# UMDK.net
KiCad netlist of a schematic drawn in Altium Designer
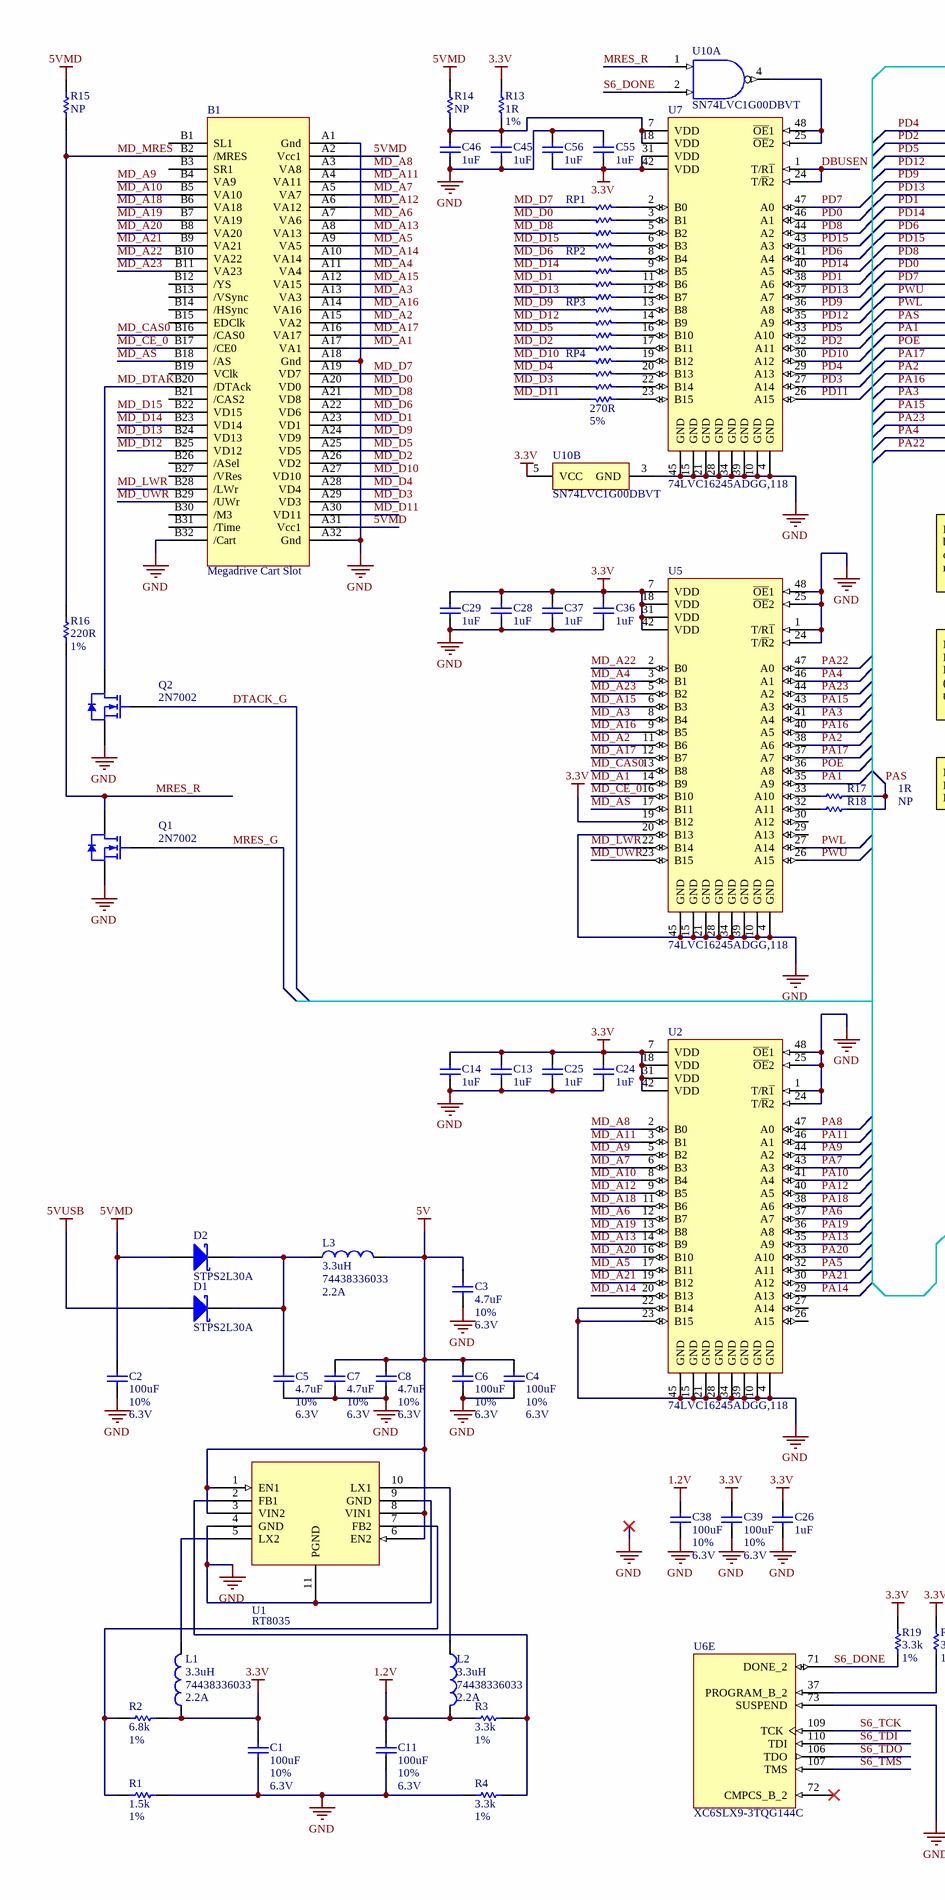
[diagram p0: UMDK.SchDoc, left]
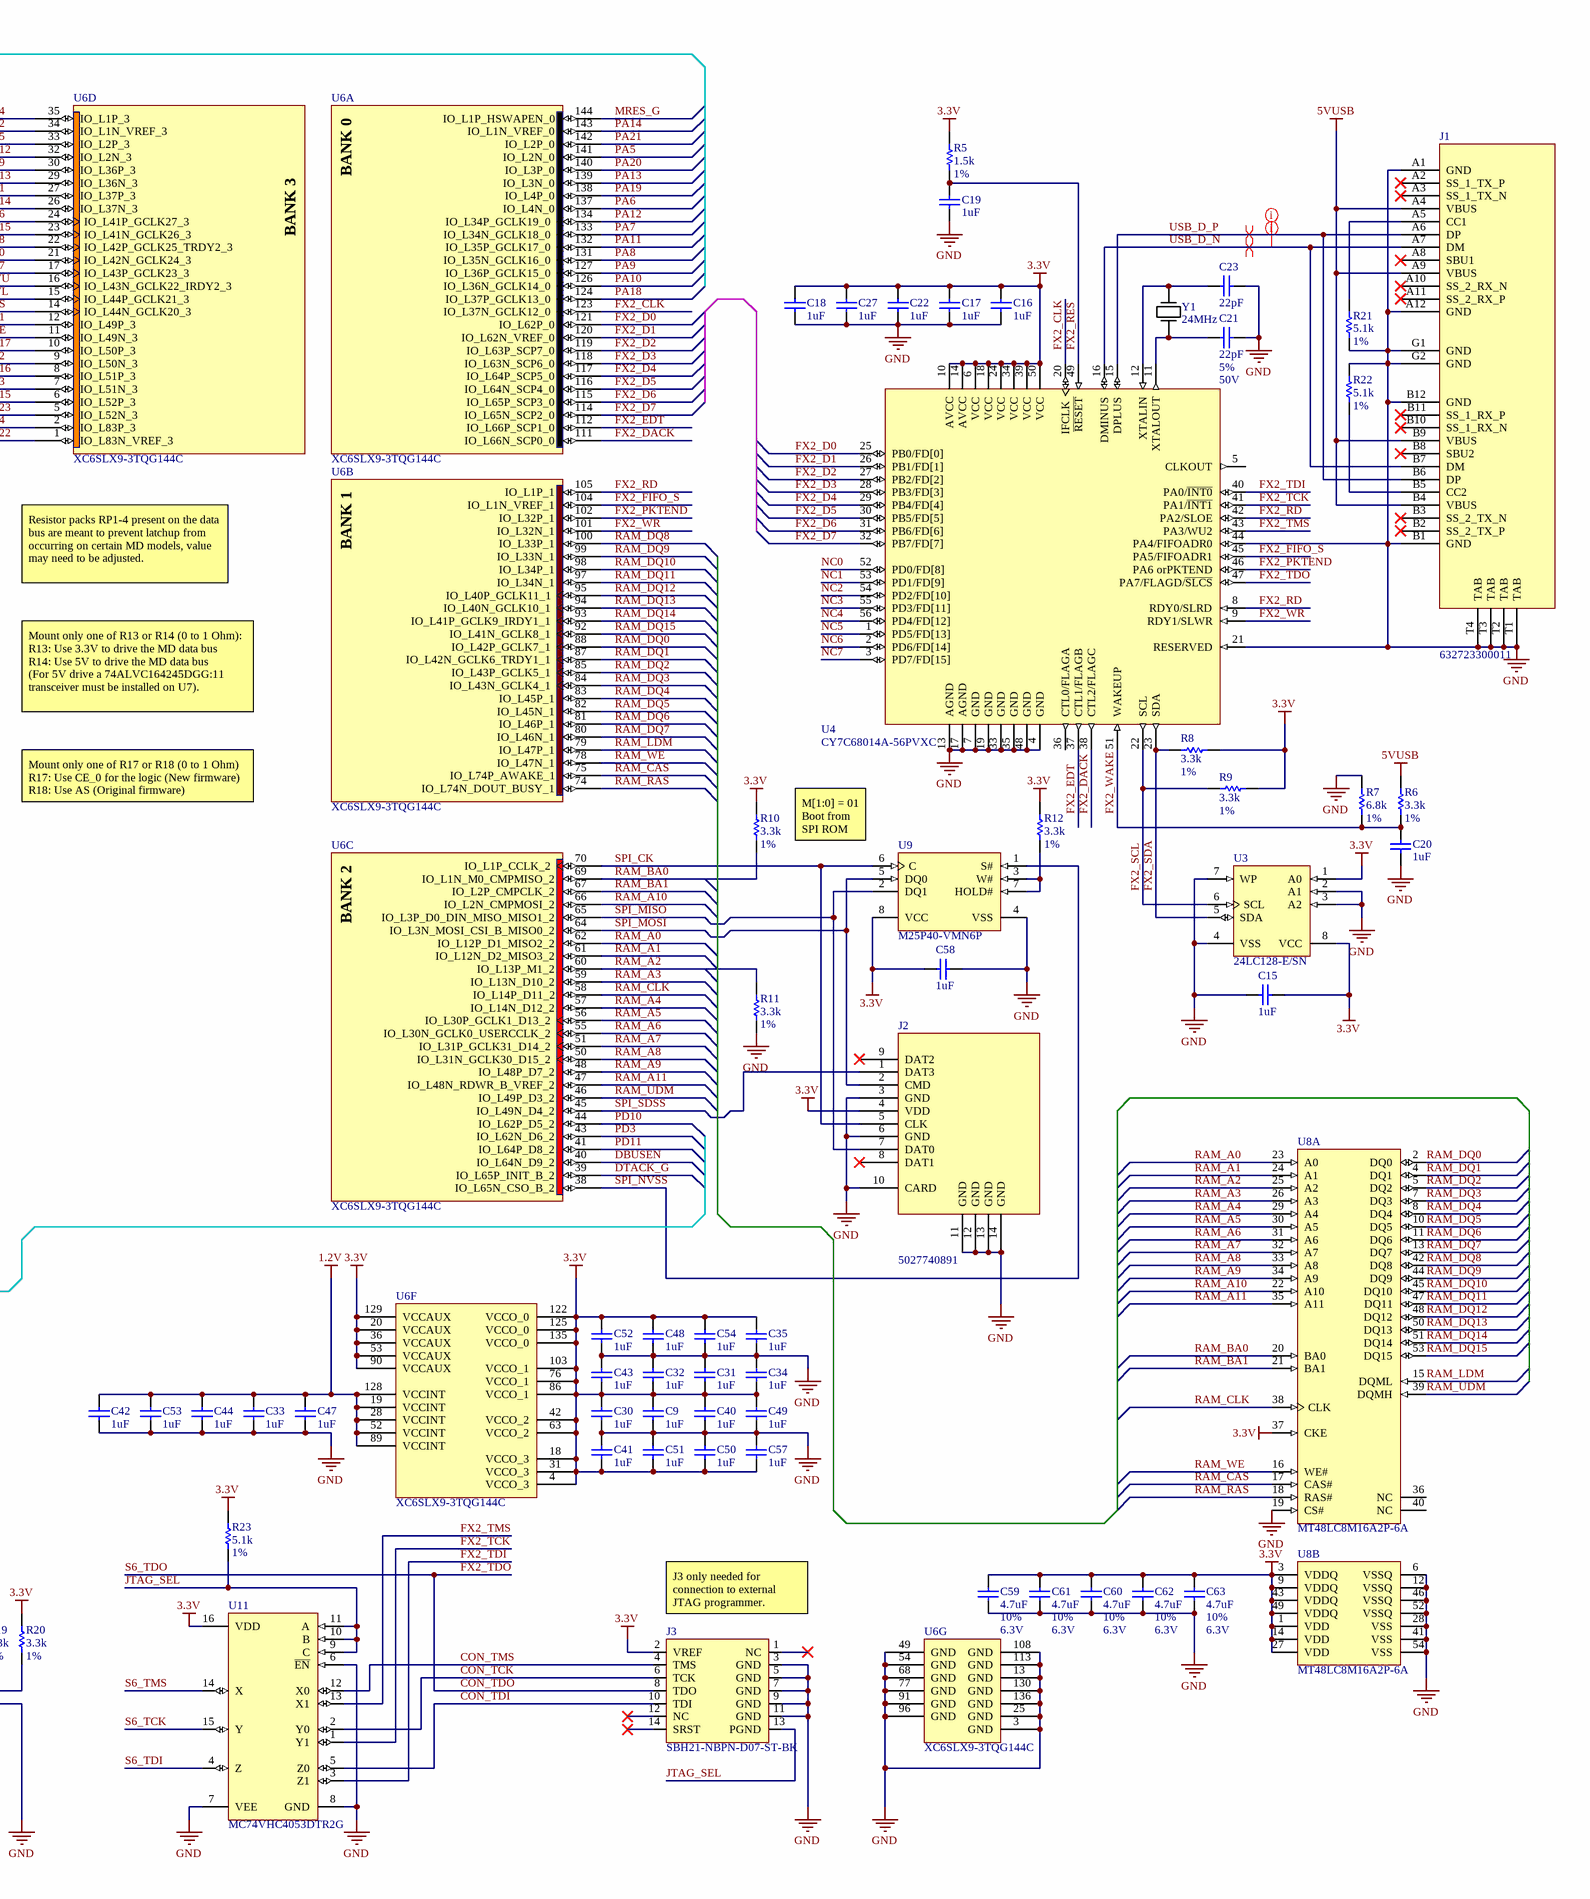
[diagram p1: UMDK.SchDoc, right]

(export (version "E")
  (design (tool "Eeschema 10.0.6"))
  (components
    (comp (ref "B1")
      (value "Megadrive Cart Slot")
      (footprint "MD CART EDGE")
      (description "Megadrive Cart Edge Connector")
      (libsource (lib "UMDK") (part "Megadrive Cart Slot"))
    )
    (comp (ref "C1")
      (value "100uF")
      (footprint "C-1210")
      (description "SMD Capacitor")
      (fields
        (field (name "MANUFACTURER PART NUMBER") "C1210C107M9PAC7800")
        (field (name "MANUFACTURER") "Kemet")
        (field (name "TOLERANCE") "10%")
        (field (name "VOLTAGE") "6.3V")
      )
      (libsource (lib "UMDK") (part "CAP_SMD"))
    )
    (comp (ref "C2")
      (value "100uF")
      (footprint "C-1210")
      (description "SMD Capacitor")
      (fields
        (field (name "MANUFACTURER PART NUMBER") "C1210C107M9PAC7800")
        (field (name "MANUFACTURER") "Kemet")
        (field (name "TOLERANCE") "10%")
        (field (name "VOLTAGE") "6.3V")
      )
      (libsource (lib "UMDK") (part "CAP_SMD"))
    )
    (comp (ref "C3")
      (value "4.7uF")
      (footprint "C-0603")
      (description "SMD Capacitor")
      (fields
        (field (name "MANUFACTURER PART NUMBER") "C0603C475K9PAC7867")
        (field (name "MANUFACTURER") "Kemet")
        (field (name "TOLERANCE") "10%")
        (field (name "VOLTAGE") "6.3V")
      )
      (libsource (lib "UMDK") (part "CAP_SMD"))
    )
    (comp (ref "C4")
      (value "100uF")
      (footprint "C-1210")
      (description "SMD Capacitor")
      (fields
        (field (name "MANUFACTURER PART NUMBER") "C1210C107M9PAC7800")
        (field (name "MANUFACTURER") "Kemet")
        (field (name "TOLERANCE") "10%")
        (field (name "VOLTAGE") "6.3V")
      )
      (libsource (lib "UMDK") (part "CAP_SMD"))
    )
    (comp (ref "C5")
      (value "4.7uF")
      (footprint "C-0603")
      (description "SMD Capacitor")
      (fields
        (field (name "MANUFACTURER PART NUMBER") "C0603C475K9PAC7867")
        (field (name "MANUFACTURER") "Kemet")
        (field (name "TOLERANCE") "10%")
        (field (name "VOLTAGE") "6.3V")
      )
      (libsource (lib "UMDK") (part "CAP_SMD"))
    )
    (comp (ref "C6")
      (value "100uF")
      (footprint "C-1210")
      (description "SMD Capacitor")
      (fields
        (field (name "MANUFACTURER PART NUMBER") "C1210C107M9PAC7800")
        (field (name "MANUFACTURER") "Kemet")
        (field (name "TOLERANCE") "10%")
        (field (name "VOLTAGE") "6.3V")
      )
      (libsource (lib "UMDK") (part "CAP_SMD"))
    )
    (comp (ref "C7")
      (value "4.7uF")
      (footprint "C-0603")
      (description "SMD Capacitor")
      (fields
        (field (name "MANUFACTURER PART NUMBER") "C0603C475K9PAC7867")
        (field (name "MANUFACTURER") "Kemet")
        (field (name "TOLERANCE") "10%")
        (field (name "VOLTAGE") "6.3V")
      )
      (libsource (lib "UMDK") (part "CAP_SMD"))
    )
    (comp (ref "C8")
      (value "4.7uF")
      (footprint "C-0603")
      (description "SMD Capacitor")
      (fields
        (field (name "MANUFACTURER PART NUMBER") "C0603C475K9PAC7867")
        (field (name "MANUFACTURER") "Kemet")
        (field (name "TOLERANCE") "10%")
        (field (name "VOLTAGE") "6.3V")
      )
      (libsource (lib "UMDK") (part "CAP_SMD"))
    )
    (comp (ref "C9")
      (value "1uF")
      (footprint "C-0402")
      (description "SMD Capacitor")
      (fields
        (field (name "MANUFACTURER PART NUMBER") "C0402C105K9PAC7867")
        (field (name "MANUFACTURER") "Kemet")
      )
      (libsource (lib "UMDK") (part "CAP_SMD"))
    )
    (comp (ref "C11")
      (value "100uF")
      (footprint "C-1210")
      (description "SMD Capacitor")
      (fields
        (field (name "MANUFACTURER PART NUMBER") "C1210C107M9PAC7800")
        (field (name "MANUFACTURER") "Kemet")
        (field (name "TOLERANCE") "10%")
        (field (name "VOLTAGE") "6.3V")
      )
      (libsource (lib "UMDK") (part "CAP_SMD"))
    )
    (comp (ref "C13")
      (value "1uF")
      (footprint "C-0402")
      (description "SMD Capacitor")
      (fields
        (field (name "MANUFACTURER PART NUMBER") "C0402C105K9PAC7867")
        (field (name "MANUFACTURER") "Kemet")
      )
      (libsource (lib "UMDK") (part "CAP_SMD"))
    )
    (comp (ref "C14")
      (value "1uF")
      (footprint "C-0402")
      (description "SMD Capacitor")
      (fields
        (field (name "MANUFACTURER PART NUMBER") "C0402C105K9PAC7867")
        (field (name "MANUFACTURER") "Kemet")
      )
      (libsource (lib "UMDK") (part "CAP_SMD"))
    )
    (comp (ref "C15")
      (value "1uF")
      (footprint "C-0402")
      (description "SMD Capacitor")
      (fields
        (field (name "MANUFACTURER PART NUMBER") "C0402C105K9PAC7867")
        (field (name "MANUFACTURER") "Kemet")
      )
      (libsource (lib "UMDK") (part "CAP_SMD"))
    )
    (comp (ref "C16")
      (value "1uF")
      (footprint "C-0402")
      (description "SMD Capacitor")
      (fields
        (field (name "MANUFACTURER PART NUMBER") "C0402C105K9PAC7867")
        (field (name "MANUFACTURER") "Kemet")
      )
      (libsource (lib "UMDK") (part "CAP_SMD"))
    )
    (comp (ref "C17")
      (value "1uF")
      (footprint "C-0402")
      (description "SMD Capacitor")
      (fields
        (field (name "MANUFACTURER PART NUMBER") "C0402C105K9PAC7867")
        (field (name "MANUFACTURER") "Kemet")
      )
      (libsource (lib "UMDK") (part "CAP_SMD"))
    )
    (comp (ref "C18")
      (value "1uF")
      (footprint "C-0402")
      (description "SMD Capacitor")
      (fields
        (field (name "MANUFACTURER PART NUMBER") "C0402C105K9PAC7867")
        (field (name "MANUFACTURER") "Kemet")
      )
      (libsource (lib "UMDK") (part "CAP_SMD"))
    )
    (comp (ref "C19")
      (value "1uF")
      (footprint "C-0402")
      (description "SMD Capacitor")
      (fields
        (field (name "MANUFACTURER PART NUMBER") "C0402C105K9PAC7867")
        (field (name "MANUFACTURER") "Kemet")
      )
      (libsource (lib "UMDK") (part "CAP_SMD"))
    )
    (comp (ref "C20")
      (value "1uF")
      (footprint "C-0402")
      (description "SMD Capacitor")
      (fields
        (field (name "MANUFACTURER PART NUMBER") "C0402C105K9PAC7867")
        (field (name "MANUFACTURER") "Kemet")
      )
      (libsource (lib "UMDK") (part "CAP_SMD"))
    )
    (comp (ref "C21")
      (value "22pF")
      (footprint "C-0402")
      (description "SMD Capacitor")
      (fields
        (field (name "MANUFACTURER PART NUMBER") "C0402C220J5GACTU")
        (field (name "MANUFACTURER") "Kemet")
        (field (name "TOLERANCE") "5%")
        (field (name "VOLTAGE") "50V")
      )
      (libsource (lib "UMDK") (part "CAP_SMD"))
    )
    (comp (ref "C22")
      (value "1uF")
      (footprint "C-0402")
      (description "SMD Capacitor")
      (fields
        (field (name "MANUFACTURER PART NUMBER") "C0402C105K9PAC7867")
        (field (name "MANUFACTURER") "Kemet")
      )
      (libsource (lib "UMDK") (part "CAP_SMD"))
    )
    (comp (ref "C23")
      (value "22pF")
      (footprint "C-0402")
      (description "SMD Capacitor")
      (fields
        (field (name "MANUFACTURER PART NUMBER") "C0402C220J5GACTU")
        (field (name "MANUFACTURER") "Kemet")
      )
      (libsource (lib "UMDK") (part "CAP_SMD"))
    )
    (comp (ref "C24")
      (value "1uF")
      (footprint "C-0402")
      (description "SMD Capacitor")
      (fields
        (field (name "MANUFACTURER PART NUMBER") "C0402C105K9PAC7867")
        (field (name "MANUFACTURER") "Kemet")
      )
      (libsource (lib "UMDK") (part "CAP_SMD"))
    )
    (comp (ref "C25")
      (value "1uF")
      (footprint "C-0402")
      (description "SMD Capacitor")
      (fields
        (field (name "MANUFACTURER PART NUMBER") "C0402C105K9PAC7867")
        (field (name "MANUFACTURER") "Kemet")
      )
      (libsource (lib "UMDK") (part "CAP_SMD"))
    )
    (comp (ref "C26")
      (value "1uF")
      (footprint "C-0402")
      (description "SMD Capacitor")
      (fields
        (field (name "MANUFACTURER PART NUMBER") "C0402C105K9PAC7867")
        (field (name "MANUFACTURER") "Kemet")
      )
      (libsource (lib "UMDK") (part "CAP_SMD"))
    )
    (comp (ref "C27")
      (value "1uF")
      (footprint "C-0402")
      (description "SMD Capacitor")
      (fields
        (field (name "MANUFACTURER PART NUMBER") "C0402C105K9PAC7867")
        (field (name "MANUFACTURER") "Kemet")
      )
      (libsource (lib "UMDK") (part "CAP_SMD"))
    )
    (comp (ref "C28")
      (value "1uF")
      (footprint "C-0402")
      (description "SMD Capacitor")
      (fields
        (field (name "MANUFACTURER PART NUMBER") "C0402C105K9PAC7867")
        (field (name "MANUFACTURER") "Kemet")
      )
      (libsource (lib "UMDK") (part "CAP_SMD"))
    )
    (comp (ref "C29")
      (value "1uF")
      (footprint "C-0402")
      (description "SMD Capacitor")
      (fields
        (field (name "MANUFACTURER PART NUMBER") "C0402C105K9PAC7867")
        (field (name "MANUFACTURER") "Kemet")
      )
      (libsource (lib "UMDK") (part "CAP_SMD"))
    )
    (comp (ref "C30")
      (value "1uF")
      (footprint "C-0402")
      (description "SMD Capacitor")
      (fields
        (field (name "MANUFACTURER PART NUMBER") "C0402C105K9PAC7867")
        (field (name "MANUFACTURER") "Kemet")
      )
      (libsource (lib "UMDK") (part "CAP_SMD"))
    )
    (comp (ref "C31")
      (value "1uF")
      (footprint "C-0402")
      (description "SMD Capacitor")
      (fields
        (field (name "MANUFACTURER PART NUMBER") "C0402C105K9PAC7867")
        (field (name "MANUFACTURER") "Kemet")
      )
      (libsource (lib "UMDK") (part "CAP_SMD"))
    )
    (comp (ref "C32")
      (value "1uF")
      (footprint "C-0402")
      (description "SMD Capacitor")
      (fields
        (field (name "MANUFACTURER PART NUMBER") "C0402C105K9PAC7867")
        (field (name "MANUFACTURER") "Kemet")
      )
      (libsource (lib "UMDK") (part "CAP_SMD"))
    )
    (comp (ref "C33")
      (value "1uF")
      (footprint "C-0402")
      (description "SMD Capacitor")
      (fields
        (field (name "MANUFACTURER PART NUMBER") "C0402C105K9PAC7867")
        (field (name "MANUFACTURER") "Kemet")
      )
      (libsource (lib "UMDK") (part "CAP_SMD"))
    )
    (comp (ref "C34")
      (value "1uF")
      (footprint "C-0402")
      (description "SMD Capacitor")
      (fields
        (field (name "MANUFACTURER PART NUMBER") "C0402C105K9PAC7867")
        (field (name "MANUFACTURER") "Kemet")
      )
      (libsource (lib "UMDK") (part "CAP_SMD"))
    )
    (comp (ref "C35")
      (value "1uF")
      (footprint "C-0402")
      (description "SMD Capacitor")
      (fields
        (field (name "MANUFACTURER PART NUMBER") "C0402C105K9PAC7867")
        (field (name "MANUFACTURER") "Kemet")
      )
      (libsource (lib "UMDK") (part "CAP_SMD"))
    )
    (comp (ref "C36")
      (value "1uF")
      (footprint "C-0402")
      (description "SMD Capacitor")
      (fields
        (field (name "MANUFACTURER PART NUMBER") "C0402C105K9PAC7867")
        (field (name "MANUFACTURER") "Kemet")
      )
      (libsource (lib "UMDK") (part "CAP_SMD"))
    )
    (comp (ref "C37")
      (value "1uF")
      (footprint "C-0402")
      (description "SMD Capacitor")
      (fields
        (field (name "MANUFACTURER PART NUMBER") "C0402C105K9PAC7867")
        (field (name "MANUFACTURER") "Kemet")
      )
      (libsource (lib "UMDK") (part "CAP_SMD"))
    )
    (comp (ref "C38")
      (value "100uF")
      (footprint "C-1210")
      (description "SMD Capacitor")
      (fields
        (field (name "MANUFACTURER PART NUMBER") "C1210C107M9PAC7800")
        (field (name "MANUFACTURER") "Kemet")
        (field (name "TOLERANCE") "10%")
        (field (name "VOLTAGE") "6.3V")
      )
      (libsource (lib "UMDK") (part "CAP_SMD"))
    )
    (comp (ref "C39")
      (value "100uF")
      (footprint "C-1210")
      (description "SMD Capacitor")
      (fields
        (field (name "MANUFACTURER PART NUMBER") "C1210C107M9PAC7800")
        (field (name "MANUFACTURER") "Kemet")
        (field (name "TOLERANCE") "10%")
        (field (name "VOLTAGE") "6.3V")
      )
      (libsource (lib "UMDK") (part "CAP_SMD"))
    )
    (comp (ref "C40")
      (value "1uF")
      (footprint "C-0402")
      (description "SMD Capacitor")
      (fields
        (field (name "MANUFACTURER PART NUMBER") "C0402C105K9PAC7867")
        (field (name "MANUFACTURER") "Kemet")
      )
      (libsource (lib "UMDK") (part "CAP_SMD"))
    )
    (comp (ref "C41")
      (value "1uF")
      (footprint "C-0402")
      (description "SMD Capacitor")
      (fields
        (field (name "MANUFACTURER PART NUMBER") "C0402C105K9PAC7867")
        (field (name "MANUFACTURER") "Kemet")
      )
      (libsource (lib "UMDK") (part "CAP_SMD"))
    )
    (comp (ref "C42")
      (value "1uF")
      (footprint "C-0402")
      (description "SMD Capacitor")
      (fields
        (field (name "MANUFACTURER PART NUMBER") "C0402C105K9PAC7867")
        (field (name "MANUFACTURER") "Kemet")
      )
      (libsource (lib "UMDK") (part "CAP_SMD"))
    )
    (comp (ref "C43")
      (value "1uF")
      (footprint "C-0402")
      (description "SMD Capacitor")
      (fields
        (field (name "MANUFACTURER PART NUMBER") "C0402C105K9PAC7867")
        (field (name "MANUFACTURER") "Kemet")
      )
      (libsource (lib "UMDK") (part "CAP_SMD"))
    )
    (comp (ref "C44")
      (value "1uF")
      (footprint "C-0402")
      (description "SMD Capacitor")
      (fields
        (field (name "MANUFACTURER PART NUMBER") "C0402C105K9PAC7867")
        (field (name "MANUFACTURER") "Kemet")
      )
      (libsource (lib "UMDK") (part "CAP_SMD"))
    )
    (comp (ref "C45")
      (value "1uF")
      (footprint "C-0402")
      (description "SMD Capacitor")
      (fields
        (field (name "MANUFACTURER PART NUMBER") "C0402C105K9PAC7867")
        (field (name "MANUFACTURER") "Kemet")
      )
      (libsource (lib "UMDK") (part "CAP_SMD"))
    )
    (comp (ref "C46")
      (value "1uF")
      (footprint "C-0402")
      (description "SMD Capacitor")
      (fields
        (field (name "MANUFACTURER PART NUMBER") "C0402C105K9PAC7867")
        (field (name "MANUFACTURER") "Kemet")
      )
      (libsource (lib "UMDK") (part "CAP_SMD"))
    )
    (comp (ref "C47")
      (value "1uF")
      (footprint "C-0402")
      (description "SMD Capacitor")
      (fields
        (field (name "MANUFACTURER PART NUMBER") "C0402C105K9PAC7867")
        (field (name "MANUFACTURER") "Kemet")
      )
      (libsource (lib "UMDK") (part "CAP_SMD"))
    )
    (comp (ref "C48")
      (value "1uF")
      (footprint "C-0402")
      (description "SMD Capacitor")
      (fields
        (field (name "MANUFACTURER PART NUMBER") "C0402C105K9PAC7867")
        (field (name "MANUFACTURER") "Kemet")
      )
      (libsource (lib "UMDK") (part "CAP_SMD"))
    )
    (comp (ref "C49")
      (value "1uF")
      (footprint "C-0402")
      (description "SMD Capacitor")
      (fields
        (field (name "MANUFACTURER PART NUMBER") "C0402C105K9PAC7867")
        (field (name "MANUFACTURER") "Kemet")
      )
      (libsource (lib "UMDK") (part "CAP_SMD"))
    )
    (comp (ref "C50")
      (value "1uF")
      (footprint "C-0402")
      (description "SMD Capacitor")
      (fields
        (field (name "MANUFACTURER PART NUMBER") "C0402C105K9PAC7867")
        (field (name "MANUFACTURER") "Kemet")
      )
      (libsource (lib "UMDK") (part "CAP_SMD"))
    )
    (comp (ref "C51")
      (value "1uF")
      (footprint "C-0402")
      (description "SMD Capacitor")
      (fields
        (field (name "MANUFACTURER PART NUMBER") "C0402C105K9PAC7867")
        (field (name "MANUFACTURER") "Kemet")
      )
      (libsource (lib "UMDK") (part "CAP_SMD"))
    )
    (comp (ref "C52")
      (value "1uF")
      (footprint "C-0402")
      (description "SMD Capacitor")
      (fields
        (field (name "MANUFACTURER PART NUMBER") "C0402C105K9PAC7867")
        (field (name "MANUFACTURER") "Kemet")
      )
      (libsource (lib "UMDK") (part "CAP_SMD"))
    )
    (comp (ref "C53")
      (value "1uF")
      (footprint "C-0402")
      (description "SMD Capacitor")
      (fields
        (field (name "MANUFACTURER PART NUMBER") "C0402C105K9PAC7867")
        (field (name "MANUFACTURER") "Kemet")
      )
      (libsource (lib "UMDK") (part "CAP_SMD"))
    )
    (comp (ref "C54")
      (value "1uF")
      (footprint "C-0402")
      (description "SMD Capacitor")
      (fields
        (field (name "MANUFACTURER PART NUMBER") "C0402C105K9PAC7867")
        (field (name "MANUFACTURER") "Kemet")
      )
      (libsource (lib "UMDK") (part "CAP_SMD"))
    )
    (comp (ref "C55")
      (value "1uF")
      (footprint "C-0402")
      (description "SMD Capacitor")
      (fields
        (field (name "MANUFACTURER PART NUMBER") "C0402C105K9PAC7867")
        (field (name "MANUFACTURER") "Kemet")
      )
      (libsource (lib "UMDK") (part "CAP_SMD"))
    )
    (comp (ref "C56")
      (value "1uF")
      (footprint "C-0402")
      (description "SMD Capacitor")
      (fields
        (field (name "MANUFACTURER PART NUMBER") "C0402C105K9PAC7867")
        (field (name "MANUFACTURER") "Kemet")
      )
      (libsource (lib "UMDK") (part "CAP_SMD"))
    )
    (comp (ref "C57")
      (value "1uF")
      (footprint "C-0402")
      (description "SMD Capacitor")
      (fields
        (field (name "MANUFACTURER PART NUMBER") "C0402C105K9PAC7867")
        (field (name "MANUFACTURER") "Kemet")
      )
      (libsource (lib "UMDK") (part "CAP_SMD"))
    )
    (comp (ref "C58")
      (value "1uF")
      (footprint "C-0402")
      (description "SMD Capacitor")
      (fields
        (field (name "MANUFACTURER PART NUMBER") "C0402C105K9PAC7867")
        (field (name "MANUFACTURER") "Kemet")
      )
      (libsource (lib "UMDK") (part "CAP_SMD"))
    )
    (comp (ref "C59")
      (value "4.7uF")
      (footprint "C-0603")
      (description "SMD Capacitor")
      (fields
        (field (name "MANUFACTURER PART NUMBER") "C0603C475K9PAC7867")
        (field (name "MANUFACTURER") "Kemet")
        (field (name "TOLERANCE") "10%")
        (field (name "VOLTAGE") "6.3V")
      )
      (libsource (lib "UMDK") (part "CAP_SMD"))
    )
    (comp (ref "C60")
      (value "4.7uF")
      (footprint "C-0603")
      (description "SMD Capacitor")
      (fields
        (field (name "MANUFACTURER PART NUMBER") "C0603C475K9PAC7867")
        (field (name "MANUFACTURER") "Kemet")
        (field (name "TOLERANCE") "10%")
        (field (name "VOLTAGE") "6.3V")
      )
      (libsource (lib "UMDK") (part "CAP_SMD"))
    )
    (comp (ref "C61")
      (value "4.7uF")
      (footprint "C-0603")
      (description "SMD Capacitor")
      (fields
        (field (name "MANUFACTURER PART NUMBER") "C0603C475K9PAC7867")
        (field (name "MANUFACTURER") "Kemet")
        (field (name "TOLERANCE") "10%")
        (field (name "VOLTAGE") "6.3V")
      )
      (libsource (lib "UMDK") (part "CAP_SMD"))
    )
    (comp (ref "C62")
      (value "4.7uF")
      (footprint "C-0603")
      (description "SMD Capacitor")
      (fields
        (field (name "MANUFACTURER PART NUMBER") "C0603C475K9PAC7867")
        (field (name "MANUFACTURER") "Kemet")
        (field (name "TOLERANCE") "10%")
        (field (name "VOLTAGE") "6.3V")
      )
      (libsource (lib "UMDK") (part "CAP_SMD"))
    )
    (comp (ref "C63")
      (value "4.7uF")
      (footprint "C-0603")
      (description "SMD Capacitor")
      (fields
        (field (name "MANUFACTURER PART NUMBER") "C0603C475K9PAC7867")
        (field (name "MANUFACTURER") "Kemet")
        (field (name "TOLERANCE") "10%")
        (field (name "VOLTAGE") "6.3V")
      )
      (libsource (lib "UMDK") (part "CAP_SMD"))
    )
    (comp (ref "D1")
      (value "B230A-13-F")
      (footprint "D-SMA")
      (description "Schottky Diode")
      (fields
        (field (name "MANUFACTURER") "ST Microelectronics")
        (field (name "MANUFACTURER PART NUMBER") "STPS2L30A")
      )
      (libsource (lib "UMDK") (part "Schottky_SMD"))
    )
    (comp (ref "D2")
      (value "B230A-13-F")
      (footprint "D-SMA")
      (description "Schottky Diode")
      (fields
        (field (name "MANUFACTURER") "ST Microelectronics")
        (field (name "MANUFACTURER PART NUMBER") "STPS2L30A")
      )
      (libsource (lib "UMDK") (part "Schottky_SMD"))
    )
    (comp (ref "J1")
      (value "632723300011")
      (footprint "632723300011")
      (fields (field (name "MANUFACTURER") "Wuerth Elektronik"))
      (libsource (lib "UMDK") (part "632723300011"))
    )
    (comp (ref "J2")
      (value "5027740891")
      (footprint "5027740891")
      (description "Micro SDCard Slot Push Push")
      (fields (field (name "MANUFACTURER") "Molex"))
      (libsource (lib "UMDK") (part "5027740891"))
    )
    (comp (ref "J3")
      (value "SBH21-NBPN-D07-ST-BK")
      (footprint "AWHW2 14G-0202")
      (fields (field (name "MANUFACTURER") "Sullins Connector Solutions"))
      (libsource (lib "UMDK") (part "XILINX JTAG"))
    )
    (comp (ref "L1")
      (value "3.3uH")
      (footprint "I-1212")
      (description "SMD Inductor")
      (fields
        (field (name "TOLERANCE") "20%")
        (field (name "MANUFACTURER") "Wuerth Elektronik")
        (field (name "MANUFACTURER PART NUMBER") "74438336033")
        (field (name "CURRENT") "2.2A")
      )
      (libsource (lib "UMDK") (part "IND_SMD"))
    )
    (comp (ref "L2")
      (value "3.3uH")
      (footprint "I-1212")
      (description "SMD Inductor")
      (fields
        (field (name "TOLERANCE") "20%")
        (field (name "MANUFACTURER") "Wuerth Elektronik")
        (field (name "MANUFACTURER PART NUMBER") "74438336033")
        (field (name "CURRENT") "2.2A")
      )
      (libsource (lib "UMDK") (part "IND_SMD"))
    )
    (comp (ref "L3")
      (value "3.3uH")
      (footprint "I-1212")
      (description "SMD Inductor")
      (fields
        (field (name "TOLERANCE") "20%")
        (field (name "MANUFACTURER") "Wuerth Elektronik")
        (field (name "MANUFACTURER PART NUMBER") "74438336033")
        (field (name "CURRENT") "2.2A")
      )
      (libsource (lib "UMDK") (part "IND_SMD"))
    )
    (comp (ref "Q1")
      (value "2N7002")
      (footprint "T-SOT23")
      (description "N-Channel Mosfet")
      (fields (field (name "MANUFACTURER") "Nexperia") (field (name "MANUFACTURER PART NUMBER") "2N7002,215"))
      (libsource (lib "UMDK") (part "NMOS_SMD"))
    )
    (comp (ref "Q2")
      (value "2N7002")
      (footprint "T-SOT23")
      (description "N-Channel Mosfet")
      (fields (field (name "MANUFACTURER") "Nexperia") (field (name "MANUFACTURER PART NUMBER") "2N7002,215"))
      (libsource (lib "UMDK") (part "NMOS_SMD"))
    )
    (comp (ref "R1")
      (value "1.5k")
      (footprint "R-0402")
      (description "SMD Resistor")
      (fields
        (field (name "MANUFACTURER PART NUMBER") "CRCW04021K50FKEDC")
        (field (name "MANUFACTURER") "Vishay")
        (field (name "TOLERANCE") "1%")
      )
      (libsource (lib "UMDK") (part "RES_SMD"))
    )
    (comp (ref "R2")
      (value "6.8k")
      (footprint "R-0402")
      (description "SMD Resistor")
      (fields
        (field (name "MANUFACTURER PART NUMBER") "CRCW04026K80FKEDC")
        (field (name "MANUFACTURER") "Vishay")
        (field (name "TOLERANCE") "1%")
      )
      (libsource (lib "UMDK") (part "RES_SMD"))
    )
    (comp (ref "R3")
      (value "3.3k")
      (footprint "R-0402")
      (description "SMD Resistor")
      (fields
        (field (name "MANUFACTURER PART NUMBER") "CRCW04023K30FKEDC")
        (field (name "MANUFACTURER") "Vishay")
        (field (name "TOLERANCE") "1%")
      )
      (libsource (lib "UMDK") (part "RES_SMD"))
    )
    (comp (ref "R4")
      (value "3.3k")
      (footprint "R-0402")
      (description "SMD Resistor")
      (fields
        (field (name "MANUFACTURER PART NUMBER") "CRCW04023K30FKEDC")
        (field (name "MANUFACTURER") "Vishay")
        (field (name "TOLERANCE") "1%")
      )
      (libsource (lib "UMDK") (part "RES_SMD"))
    )
    (comp (ref "R5")
      (value "1.5k")
      (footprint "R-0402")
      (description "SMD Resistor")
      (fields
        (field (name "MANUFACTURER PART NUMBER") "CRCW04021K50FKEDC")
        (field (name "MANUFACTURER") "Vishay")
        (field (name "TOLERANCE") "1%")
      )
      (libsource (lib "UMDK") (part "RES_SMD"))
    )
    (comp (ref "R6")
      (value "3.3k")
      (footprint "R-0402")
      (description "SMD Resistor")
      (fields
        (field (name "MANUFACTURER PART NUMBER") "CRCW04023K30FKEDC")
        (field (name "MANUFACTURER") "Vishay")
        (field (name "TOLERANCE") "1%")
      )
      (libsource (lib "UMDK") (part "RES_SMD"))
    )
    (comp (ref "R7")
      (value "6.8k")
      (footprint "R-0402")
      (description "SMD Resistor")
      (fields
        (field (name "MANUFACTURER PART NUMBER") "CRCW04026K80FKEDC")
        (field (name "MANUFACTURER") "Vishay")
        (field (name "TOLERANCE") "1%")
      )
      (libsource (lib "UMDK") (part "RES_SMD"))
    )
    (comp (ref "R8")
      (value "3.3k")
      (footprint "R-0402")
      (description "SMD Resistor")
      (fields
        (field (name "MANUFACTURER PART NUMBER") "CRCW04023K30FKEDC")
        (field (name "MANUFACTURER") "Vishay")
        (field (name "TOLERANCE") "1%")
      )
      (libsource (lib "UMDK") (part "RES_SMD"))
    )
    (comp (ref "R9")
      (value "3.3k")
      (footprint "R-0402")
      (description "SMD Resistor")
      (fields
        (field (name "MANUFACTURER PART NUMBER") "CRCW04023K30FKEDC")
        (field (name "MANUFACTURER") "Vishay")
        (field (name "TOLERANCE") "1%")
      )
      (libsource (lib "UMDK") (part "RES_SMD"))
    )
    (comp (ref "R10")
      (value "3.3k")
      (footprint "R-0402")
      (description "SMD Resistor")
      (fields
        (field (name "MANUFACTURER PART NUMBER") "CRCW04023K30FKEDC")
        (field (name "MANUFACTURER") "Vishay")
        (field (name "TOLERANCE") "1%")
      )
      (libsource (lib "UMDK") (part "RES_SMD"))
    )
    (comp (ref "R11")
      (value "3.3k")
      (footprint "R-0402")
      (description "SMD Resistor")
      (fields
        (field (name "MANUFACTURER PART NUMBER") "CRCW04023K30FKEDC")
        (field (name "MANUFACTURER") "Vishay")
        (field (name "TOLERANCE") "1%")
      )
      (libsource (lib "UMDK") (part "RES_SMD"))
    )
    (comp (ref "R12")
      (value "3.3k")
      (footprint "R-0402")
      (description "SMD Resistor")
      (fields
        (field (name "MANUFACTURER PART NUMBER") "CRCW04023K30FKEDC")
        (field (name "MANUFACTURER") "Vishay")
        (field (name "TOLERANCE") "1%")
      )
      (libsource (lib "UMDK") (part "RES_SMD"))
    )
    (comp (ref "R13")
      (value "1R")
      (footprint "R-0402")
      (description "SMD Resistor")
      (fields
        (field (name "MANUFACTURER PART NUMBER") "CRCW04021R00FKEDC")
        (field (name "MANUFACTURER") "Vishay")
        (field (name "TOLERANCE") "1%")
      )
      (libsource (lib "UMDK") (part "RES_SMD"))
    )
    (comp (ref "R14")
      (value "NP")
      (footprint "R-0402")
      (description "SMD Resistor")
      (libsource (lib "UMDK") (part "RES_SMD"))
    )
    (comp (ref "R15")
      (value "NP")
      (footprint "R-0402")
      (description "SMD Resistor")
      (libsource (lib "UMDK") (part "RES_SMD"))
    )
    (comp (ref "R16")
      (value "220R")
      (footprint "R-0402")
      (description "SMD Resistor")
      (fields
        (field (name "MANUFACTURER PART NUMBER") "CRCW0402220RFKEDC")
        (field (name "MANUFACTURER") "Vishay")
        (field (name "TOLERANCE") "1%")
      )
      (libsource (lib "UMDK") (part "RES_SMD"))
    )
    (comp (ref "R17")
      (value "1R")
      (footprint "R-0402")
      (description "SMD Resistor")
      (fields
        (field (name "MANUFACTURER PART NUMBER") "CRCW04021R00FKEDC")
        (field (name "MANUFACTURER") "Vishay")
      )
      (libsource (lib "UMDK") (part "RES_SMD"))
    )
    (comp (ref "R18")
      (value "NP")
      (footprint "R-0402")
      (description "SMD Resistor")
      (libsource (lib "UMDK") (part "RES_SMD"))
    )
    (comp (ref "R19")
      (value "3.3k")
      (footprint "R-0402")
      (description "SMD Resistor")
      (fields
        (field (name "MANUFACTURER PART NUMBER") "CRCW04023K30FKEDC")
        (field (name "MANUFACTURER") "Vishay")
        (field (name "TOLERANCE") "1%")
      )
      (libsource (lib "UMDK") (part "RES_SMD"))
    )
    (comp (ref "R20")
      (value "3.3k")
      (footprint "R-0402")
      (description "SMD Resistor")
      (fields
        (field (name "MANUFACTURER PART NUMBER") "CRCW04023K30FKEDC")
        (field (name "MANUFACTURER") "Vishay")
        (field (name "TOLERANCE") "1%")
      )
      (libsource (lib "UMDK") (part "RES_SMD"))
    )
    (comp (ref "R21")
      (value "5.1k")
      (footprint "R-0402")
      (description "SMD Resistor")
      (fields
        (field (name "MANUFACTURER PART NUMBER") "CRCW04025K10FKEDC")
        (field (name "MANUFACTURER") "Vishay")
        (field (name "TOLERANCE") "1%")
      )
      (libsource (lib "UMDK") (part "RES_SMD"))
    )
    (comp (ref "R22")
      (value "5.1k")
      (footprint "R-0402")
      (description "SMD Resistor")
      (fields
        (field (name "MANUFACTURER PART NUMBER") "CRCW04025K10FKEDC")
        (field (name "MANUFACTURER") "Vishay")
        (field (name "TOLERANCE") "1%")
      )
      (libsource (lib "UMDK") (part "RES_SMD"))
    )
    (comp (ref "R23")
      (value "5.1k")
      (footprint "R-0402")
      (description "SMD Resistor")
      (fields
        (field (name "MANUFACTURER PART NUMBER") "CRCW04025K10FKEDC")
        (field (name "MANUFACTURER") "Vishay")
        (field (name "TOLERANCE") "1%")
      )
      (libsource (lib "UMDK") (part "RES_SMD"))
    )
    (comp (ref "RP1")
      (value "270R")
      (footprint "RP4-1206")
      (description "SMD Resistor Pack of 4")
      (fields
        (field (name "MANUFACTURER PART NUMBER") "CAT16-271J4LF")
        (field (name "MANUFACTURER") "Bourns")
      )
      (libsource (lib "UMDK") (part "RPACK4_SMD"))
    )
    (comp (ref "RP2")
      (value "270R")
      (footprint "RP4-1206")
      (description "SMD Resistor Pack of 4")
      (fields
        (field (name "MANUFACTURER PART NUMBER") "CAT16-271J4LF")
        (field (name "MANUFACTURER") "Bourns")
      )
      (libsource (lib "UMDK") (part "RPACK4_SMD"))
    )
    (comp (ref "RP3")
      (value "270R")
      (footprint "RP4-1206")
      (description "SMD Resistor Pack of 4")
      (fields
        (field (name "MANUFACTURER PART NUMBER") "CAT16-271J4LF")
        (field (name "MANUFACTURER") "Bourns")
      )
      (libsource (lib "UMDK") (part "RPACK4_SMD"))
    )
    (comp (ref "RP4")
      (value "270R")
      (footprint "RP4-1206")
      (description "SMD Resistor Pack of 4")
      (fields
        (field (name "MANUFACTURER PART NUMBER") "CAT16-271J4LF")
        (field (name "MANUFACTURER") "Bourns")
        (field (name "TOLERANCE") "5%")
      )
      (libsource (lib "UMDK") (part "RPACK4_SMD"))
    )
    (comp (ref "U1")
      (value "RT8035")
      (footprint "10SON")
      (description "DCDC Synchronous buck converter")
      (fields
        (field (name "MANUFACTURER PART NUMBER") "RT8035GQW")
        (field (name "MANUFACTURER") "Richtek USA Inc.")
      )
      (libsource (lib "UMDK") (part "RT8035"))
    )
    (comp (ref "U2")
      (value "74LVC16245ADGG,118")
      (footprint "1201-01_L")
      (description "Low-Voltage 16-Bit 3-State Non-Inverting Transceiver with 5V-Tolerant Inputs and Outputs")
      (fields (field (name "MANUFACTURER") "Nexperia"))
      (libsource (lib "UMDK") (part "MC74LCX16245DT"))
    )
    (comp (ref "U3")
      (value "24LC128-E/SN")
      (footprint "SOIC-SN8_N")
      (description "128Kbit, 400kHz, 2.5V, I2C Serial EEPROM, 8-Pin SOIC 150mil, Extended Temperature")
      (fields (field (name "MANUFACTURER") "Microchip"))
      (libsource (lib "UMDK") (part "24LC128-E/SN"))
    )
    (comp (ref "U4")
      (value "CY7C68014A-56PVXC")
      (footprint "O56_N")
      (fields (field (name "MANUFACTURER") "Cypress") (field (name "PUBLISHER") "Altium Limited"))
      (libsource (lib "UMDK") (part "CY7C68014A-56PVXC"))
    )
    (comp (ref "U5")
      (value "74LVC16245ADGG,118")
      (footprint "1201-01_L")
      (description "Low-Voltage 16-Bit 3-State Non-Inverting Transceiver with 5V-Tolerant Inputs and Outputs")
      (fields (field (name "MANUFACTURER") "Nexperia"))
      (libsource (lib "UMDK") (part "MC74LCX16245DT"))
    )
    (comp (ref "U6")
      (value "XC6SLX9-3TQG144C")
      (footprint "TQG144_N")
      (fields (field (name "MANUFACTURER") "Xilinx"))
      (libsource (lib "") (part "XC6SLX9-3TQG144C_1"))
    )
    (comp (ref "U7")
      (value "74LVC16245ADGG,118")
      (footprint "1201-01_L")
      (description "Low-Voltage 16-Bit 3-State Non-Inverting Transceiver with 5V-Tolerant Inputs and Outputs")
      (fields
        (field (name "MANUFACTURER PART NUMBER") "74ALVC164245DGG:11")
        (field (name "MANUFACTURER") "Nexperia")
      )
      (libsource (lib "UMDK") (part "MC74LCX16245DT"))
    )
    (comp (ref "U8")
      (value "MT48LC8M16A2P-6A")
      (footprint "MICT-P-54_N")
      (description "128Mb PC133 SDR SDRAM, 8Mb x 16, 6ns, 3.3V, 0 to 70 degC, 54-Pin TSOP, Pb-Free")
      (fields (field (name "VOLTAGE") "3.3V") (field (name "MANUFACTURER") "Micron"))
      (libsource (lib "UMDK") (part "MT48LC8M16A2P-6A"))
    )
    (comp (ref "U9")
      (value "M25P40-VMN6P")
      (footprint "MICT-MN-8_N")
      (description "4 Mb (x1) Serial NOR Flash Memory, 75 MHz, 2.3 to 3.6 V, 8-pin SO8 Narrow (MN), Tube")
      (fields (field (name "VOLTAGE") "2.3V-3.6V") (field (name "MANUFACTURER") "Micron"))
      (libsource (lib "UMDK") (part "M25P40-VMN6P"))
    )
    (comp (ref "U10")
      (value "SN74LVC1G00DBVT")
      (footprint "DBV0005A_N")
      (description "Single 2 Input Positive NAND Gate, DBV0005A, SMALL T&R")
      (fields
        (field (name "GENERIC PART NUMBER") "SN74LVC1G00")
        (field (name "MANUFACTURER") "Texas Instruments")
      )
      (libsource (lib "UMDK") (part "SN74LVC1G00DBVT"))
    )
    (comp (ref "U11")
      (value "MC74VHC4053DTR2G")
      (footprint "948F-01_N")
      (description "Analog Multiplexer/Demultiplexer")
      (fields (field (name "MANUFACTURER") "Onsemi") (field (name "PUBLISHER") "Altium Limited"))
      (libsource (lib "UMDK") (part "MC74VHC4053DT"))
    )
    (comp (ref "Y1")
      (value "24MHz")
      (footprint "CRYSTAL_HC49-US-SM")
      (description "Resonator Quartz 24.00 MHz 30ppm")
      (fields
        (field (name "MANUFACTURER") "CTS-Frequency Controls")
        (field (name "MANUFACTURER PART NUMBER") "ATS240BSM-1E")
      )
      (libsource (lib "UMDK") (part "Crystal_6MHz_HC49/US"))
    )
  )
  (nets
    (net (code "1") (name "/CON_TCK") (class "Default")
      (node (ref "J3") (pin "6") (pinfunction "TCK_6") (pintype "passive"))
      (node (ref "U11") (pin "2") (pinfunction "Y0_2") (pintype "bidirectional"))
    )
    (net (code "2") (name "/CON_TDI") (class "Default")
      (node (ref "J3") (pin "10") (pinfunction "TDI_10") (pintype "passive"))
      (node (ref "U11") (pin "5") (pinfunction "Z0_5") (pintype "bidirectional"))
    )
    (net (code "3") (name "/CON_TDO") (class "Default")
      (node (ref "J3") (pin "8") (pinfunction "TDO_8") (pintype "passive"))
      (node (ref "U4") (pin "47") (pinfunction "PA7/FLAGD/~{SLCS}_47") (pintype "bidirectional"))
      (node (ref "U6") (pin "106") (pinfunction "TDO_106") (pintype "output"))
    )
    (net (code "4") (name "/CON_TMS") (class "Default")
      (node (ref "J3") (pin "4") (pinfunction "TMS_4") (pintype "passive"))
      (node (ref "U11") (pin "12") (pinfunction "X0_12") (pintype "bidirectional"))
    )
    (net (code "5") (name "/DBUSEN") (class "Default")
      (node (ref "U6") (pin "40") (pinfunction "IO_L64N_D9_2_40") (pintype "bidirectional"))
      (node (ref "U7") (pin "1") (pinfunction "T/R~{1}_1") (pintype "input"))
      (node (ref "U7") (pin "24") (pinfunction "T/~{R}2_24") (pintype "input"))
    )
    (net (code "6") (name "/DTACK_G") (class "Default")
      (node (ref "Q2") (pin "1") (pinfunction "GATE_1") (pintype "passive"))
      (node (ref "U6") (pin "39") (pinfunction "IO_L65P_INIT_B_2_39") (pintype "bidirectional"))
    )
    (net (code "7") (name "/FX2_CLK") (class "Default")
      (node (ref "U4") (pin "20") (pinfunction "IFCLK_20") (pintype "bidirectional"))
      (node (ref "U6") (pin "123") (pinfunction "IO_L37N_GCLK12_0_123") (pintype "bidirectional"))
    )
    (net (code "8") (name "/FX2_D0") (class "Default")
      (node (ref "U4") (pin "25") (pinfunction "PB0/FD[0]_25") (pintype "bidirectional"))
      (node (ref "U6") (pin "121") (pinfunction "IO_L62P_0_121") (pintype "bidirectional"))
    )
    (net (code "9") (name "/FX2_D1") (class "Default")
      (node (ref "U4") (pin "26") (pinfunction "PB1/FD[1]_26") (pintype "bidirectional"))
      (node (ref "U6") (pin "120") (pinfunction "IO_L62N_VREF_0_120") (pintype "bidirectional"))
    )
    (net (code "10") (name "/FX2_D2") (class "Default")
      (node (ref "U4") (pin "27") (pinfunction "PB2/FD[2]_27") (pintype "bidirectional"))
      (node (ref "U6") (pin "119") (pinfunction "IO_L63P_SCP7_0_119") (pintype "bidirectional"))
    )
    (net (code "11") (name "/FX2_D3") (class "Default")
      (node (ref "U4") (pin "28") (pinfunction "PB3/FD[3]_28") (pintype "bidirectional"))
      (node (ref "U6") (pin "118") (pinfunction "IO_L63N_SCP6_0_118") (pintype "bidirectional"))
    )
    (net (code "12") (name "/FX2_D4") (class "Default")
      (node (ref "U4") (pin "29") (pinfunction "PB4/FD[4]_29") (pintype "bidirectional"))
      (node (ref "U6") (pin "117") (pinfunction "IO_L64P_SCP5_0_117") (pintype "bidirectional"))
    )
    (net (code "13") (name "/FX2_D5") (class "Default")
      (node (ref "U4") (pin "30") (pinfunction "PB5/FD[5]_30") (pintype "bidirectional"))
      (node (ref "U6") (pin "116") (pinfunction "IO_L64N_SCP4_0_116") (pintype "bidirectional"))
    )
    (net (code "14") (name "/FX2_D6") (class "Default")
      (node (ref "U4") (pin "31") (pinfunction "PB6/FD[6]_31") (pintype "bidirectional"))
      (node (ref "U6") (pin "115") (pinfunction "IO_L65P_SCP3_0_115") (pintype "bidirectional"))
    )
    (net (code "15") (name "/FX2_D7") (class "Default")
      (node (ref "U4") (pin "32") (pinfunction "PB7/FD[7]_32") (pintype "bidirectional"))
      (node (ref "U6") (pin "114") (pinfunction "IO_L65N_SCP2_0_114") (pintype "bidirectional"))
    )
    (net (code "16") (name "/FX2_DACK") (class "Default")
      (node (ref "U4") (pin "38") (pinfunction "CTL2/FLAGC_38") (pintype "output"))
      (node (ref "U6") (pin "111") (pinfunction "IO_L66N_SCP0_0_111") (pintype "bidirectional"))
    )
    (net (code "17") (name "/FX2_EDT") (class "Default")
      (node (ref "U4") (pin "37") (pinfunction "CTL1/FLAGB_37") (pintype "output"))
      (node (ref "U6") (pin "112") (pinfunction "IO_L66P_SCP1_0_112") (pintype "bidirectional"))
    )
    (net (code "18") (name "/FX2_FIFO_S") (class "Default")
      (node (ref "U4") (pin "45") (pinfunction "PA5/FIFOADR1_45") (pintype "bidirectional"))
      (node (ref "U6") (pin "104") (pinfunction "IO_L1N_VREF_1_104") (pintype "bidirectional"))
    )
    (net (code "19") (name "/FX2_PKTEND") (class "Default")
      (node (ref "U4") (pin "46") (pinfunction "PA6_orPKTEND_46") (pintype "bidirectional"))
      (node (ref "U6") (pin "102") (pinfunction "IO_L32P_1_102") (pintype "bidirectional"))
    )
    (net (code "20") (name "/FX2_RD") (class "Default")
      (node (ref "U4") (pin "42") (pinfunction "PA2/SLOE_42") (pintype "bidirectional"))
      (node (ref "U4") (pin "8") (pinfunction "RDY0/SLRD_8") (pintype "input"))
      (node (ref "U6") (pin "105") (pinfunction "IO_L1P_1_105") (pintype "bidirectional"))
    )
    (net (code "21") (name "/FX2_RES") (class "Default")
      (node (ref "C19") (pin "1") (pinfunction "1_1") (pintype "passive"))
      (node (ref "R5") (pin "2") (pinfunction "2_2") (pintype "passive"))
      (node (ref "U4") (pin "49") (pinfunction "~{RESET}_49") (pintype "input"))
    )
    (net (code "22") (name "/FX2_SCL") (class "Default")
      (node (ref "R9") (pin "1") (pinfunction "1_1") (pintype "passive"))
      (node (ref "U3") (pin "6") (pinfunction "SCL_6") (pintype "input"))
      (node (ref "U4") (pin "22") (pinfunction "SCL_22") (pintype "output"))
    )
    (net (code "23") (name "/FX2_SDA") (class "Default")
      (node (ref "R8") (pin "1") (pinfunction "1_1") (pintype "passive"))
      (node (ref "U3") (pin "5") (pinfunction "SDA_5") (pintype "bidirectional"))
      (node (ref "U4") (pin "23") (pinfunction "SDA_23") (pintype "output"))
    )
    (net (code "24") (name "/FX2_TCK") (class "Default")
      (node (ref "U11") (pin "1") (pinfunction "Y1_1") (pintype "bidirectional"))
      (node (ref "U4") (pin "41") (pinfunction "PA1/~{INT1}_41") (pintype "bidirectional"))
    )
    (net (code "25") (name "/FX2_TDI") (class "Default")
      (node (ref "U11") (pin "3") (pinfunction "Z1_3") (pintype "bidirectional"))
      (node (ref "U4") (pin "40") (pinfunction "PA0/~{INT0}_40") (pintype "bidirectional"))
    )
    (net (code "26") (name "/FX2_TMS") (class "Default")
      (node (ref "U11") (pin "13") (pinfunction "X1_13") (pintype "bidirectional"))
      (node (ref "U4") (pin "43") (pinfunction "PA3/WU2_43") (pintype "bidirectional"))
    )
    (net (code "27") (name "/FX2_WAKE") (class "Default")
      (node (ref "C20") (pin "1") (pinfunction "1_1") (pintype "passive"))
      (node (ref "R6") (pin "2") (pinfunction "2_2") (pintype "passive"))
      (node (ref "R7") (pin "1") (pinfunction "1_1") (pintype "passive"))
      (node (ref "U4") (pin "51") (pinfunction "WAKEUP_51") (pintype "input"))
    )
    (net (code "28") (name "/FX2_WR") (class "Default")
      (node (ref "U4") (pin "9") (pinfunction "RDY1/SLWR_9") (pintype "input"))
      (node (ref "U6") (pin "101") (pinfunction "IO_L32N_1_101") (pintype "bidirectional"))
    )
    (net (code "29") (name "/JTAG_SEL") (class "Default")
      (node (ref "J3") (pin "13") (pinfunction "PGND_13") (pintype "passive"))
      (node (ref "R23") (pin "2") (pinfunction "2_2") (pintype "passive"))
      (node (ref "U11") (pin "10") (pinfunction "B_10") (pintype "input"))
      (node (ref "U11") (pin "11") (pinfunction "A_11") (pintype "input"))
      (node (ref "U11") (pin "9") (pinfunction "C_9") (pintype "input"))
    )
    (net (code "30") (name "/MD_A1") (class "Default")
      (node (ref "B1") (pin "A17") (pinfunction "VA1_A17") (pintype "passive"))
      (node (ref "U5") (pin "14") (pinfunction "B9_14") (pintype "bidirectional"))
    )
    (net (code "31") (name "/MD_A2") (class "Default")
      (node (ref "B1") (pin "A15") (pinfunction "VA2_A15") (pintype "passive"))
      (node (ref "U5") (pin "11") (pinfunction "B6_11") (pintype "bidirectional"))
    )
    (net (code "32") (name "/MD_A3") (class "Default")
      (node (ref "B1") (pin "A13") (pinfunction "VA3_A13") (pintype "passive"))
      (node (ref "U5") (pin "8") (pinfunction "B4_8") (pintype "bidirectional"))
    )
    (net (code "33") (name "/MD_A4") (class "Default")
      (node (ref "B1") (pin "A11") (pinfunction "VA4_A11") (pintype "passive"))
      (node (ref "U5") (pin "3") (pinfunction "B1_3") (pintype "bidirectional"))
    )
    (net (code "34") (name "/MD_A5") (class "Default")
      (node (ref "B1") (pin "A9") (pinfunction "VA5_A9") (pintype "passive"))
      (node (ref "U2") (pin "17") (pinfunction "B11_17") (pintype "bidirectional"))
    )
    (net (code "35") (name "/MD_A6") (class "Default")
      (node (ref "B1") (pin "A7") (pinfunction "VA6_A7") (pintype "passive"))
      (node (ref "U2") (pin "12") (pinfunction "B7_12") (pintype "bidirectional"))
    )
    (net (code "36") (name "/MD_A7") (class "Default")
      (node (ref "B1") (pin "A5") (pinfunction "VA7_A5") (pintype "passive"))
      (node (ref "U2") (pin "6") (pinfunction "B3_6") (pintype "bidirectional"))
    )
    (net (code "37") (name "/MD_A8") (class "Default")
      (node (ref "B1") (pin "A3") (pinfunction "VA8_A3") (pintype "passive"))
      (node (ref "U2") (pin "2") (pinfunction "B0_2") (pintype "bidirectional"))
    )
    (net (code "38") (name "/MD_A9") (class "Default")
      (node (ref "B1") (pin "B4") (pinfunction "VA9_B4") (pintype "passive"))
      (node (ref "U2") (pin "5") (pinfunction "B2_5") (pintype "bidirectional"))
    )
    (net (code "39") (name "/MD_A10") (class "Default")
      (node (ref "B1") (pin "B5") (pinfunction "VA10_B5") (pintype "passive"))
      (node (ref "U2") (pin "8") (pinfunction "B4_8") (pintype "bidirectional"))
    )
    (net (code "40") (name "/MD_A11") (class "Default")
      (node (ref "B1") (pin "A4") (pinfunction "VA11_A4") (pintype "passive"))
      (node (ref "U2") (pin "3") (pinfunction "B1_3") (pintype "bidirectional"))
    )
    (net (code "41") (name "/MD_A12") (class "Default")
      (node (ref "B1") (pin "A6") (pinfunction "VA12_A6") (pintype "passive"))
      (node (ref "U2") (pin "9") (pinfunction "B5_9") (pintype "bidirectional"))
    )
    (net (code "42") (name "/MD_A13") (class "Default")
      (node (ref "B1") (pin "A8") (pinfunction "VA13_A8") (pintype "passive"))
      (node (ref "U2") (pin "14") (pinfunction "B9_14") (pintype "bidirectional"))
    )
    (net (code "43") (name "/MD_A14") (class "Default")
      (node (ref "B1") (pin "A10") (pinfunction "VA14_A10") (pintype "passive"))
      (node (ref "U2") (pin "20") (pinfunction "B13_20") (pintype "bidirectional"))
    )
    (net (code "44") (name "/MD_A15") (class "Default")
      (node (ref "B1") (pin "A12") (pinfunction "VA15_A12") (pintype "passive"))
      (node (ref "U5") (pin "6") (pinfunction "B3_6") (pintype "bidirectional"))
    )
    (net (code "45") (name "/MD_A16") (class "Default")
      (node (ref "B1") (pin "A14") (pinfunction "VA16_A14") (pintype "passive"))
      (node (ref "U5") (pin "9") (pinfunction "B5_9") (pintype "bidirectional"))
    )
    (net (code "46") (name "/MD_A17") (class "Default")
      (node (ref "B1") (pin "A16") (pinfunction "VA17_A16") (pintype "passive"))
      (node (ref "U5") (pin "12") (pinfunction "B7_12") (pintype "bidirectional"))
    )
    (net (code "47") (name "/MD_A18") (class "Default")
      (node (ref "B1") (pin "B6") (pinfunction "VA18_B6") (pintype "passive"))
      (node (ref "U2") (pin "11") (pinfunction "B6_11") (pintype "bidirectional"))
    )
    (net (code "48") (name "/MD_A19") (class "Default")
      (node (ref "B1") (pin "B7") (pinfunction "VA19_B7") (pintype "passive"))
      (node (ref "U2") (pin "13") (pinfunction "B8_13") (pintype "bidirectional"))
    )
    (net (code "49") (name "/MD_A20") (class "Default")
      (node (ref "B1") (pin "B8") (pinfunction "VA20_B8") (pintype "passive"))
      (node (ref "U2") (pin "16") (pinfunction "B10_16") (pintype "bidirectional"))
    )
    (net (code "50") (name "/MD_A21") (class "Default")
      (node (ref "B1") (pin "B9") (pinfunction "VA21_B9") (pintype "passive"))
      (node (ref "U2") (pin "19") (pinfunction "B12_19") (pintype "bidirectional"))
    )
    (net (code "51") (name "/MD_A22") (class "Default")
      (node (ref "B1") (pin "B10") (pinfunction "VA22_B10") (pintype "passive"))
      (node (ref "U5") (pin "2") (pinfunction "B0_2") (pintype "bidirectional"))
    )
    (net (code "52") (name "/MD_A23") (class "Default")
      (node (ref "B1") (pin "B11") (pinfunction "VA23_B11") (pintype "passive"))
      (node (ref "U5") (pin "5") (pinfunction "B2_5") (pintype "bidirectional"))
    )
    (net (code "53") (name "/MD_AS") (class "Default")
      (node (ref "B1") (pin "B18") (pinfunction "/AS_B18") (pintype "passive"))
      (node (ref "U5") (pin "17") (pinfunction "B11_17") (pintype "bidirectional"))
    )
    (net (code "54") (name "/MD_CAS0") (class "Default")
      (node (ref "B1") (pin "B16") (pinfunction "/CAS0_B16") (pintype "passive"))
      (node (ref "U5") (pin "13") (pinfunction "B8_13") (pintype "bidirectional"))
    )
    (net (code "55") (name "/MD_CE_0") (class "Default")
      (node (ref "B1") (pin "B17") (pinfunction "/CE0_B17") (pintype "passive"))
      (node (ref "U5") (pin "16") (pinfunction "B10_16") (pintype "bidirectional"))
    )
    (net (code "56") (name "/MD_D0") (class "Default")
      (node (ref "B1") (pin "A20") (pinfunction "VD0_A20") (pintype "passive"))
      (node (ref "RP1") (pin "6") (pinfunction "6_6") (pintype "passive"))
    )
    (net (code "57") (name "/MD_D1") (class "Default")
      (node (ref "B1") (pin "A23") (pinfunction "VD1_A23") (pintype "passive"))
      (node (ref "RP2") (pin "4") (pinfunction "4_4") (pintype "passive"))
    )
    (net (code "58") (name "/MD_D2") (class "Default")
      (node (ref "B1") (pin "A26") (pinfunction "VD2_A26") (pintype "passive"))
      (node (ref "RP3") (pin "2") (pinfunction "2_2") (pintype "passive"))
    )
    (net (code "59") (name "/MD_D3") (class "Default")
      (node (ref "B1") (pin "A29") (pinfunction "VD3_A29") (pintype "passive"))
      (node (ref "RP4") (pin "4") (pinfunction "4_4") (pintype "passive"))
    )
    (net (code "60") (name "/MD_D4") (class "Default")
      (node (ref "B1") (pin "A28") (pinfunction "VD4_A28") (pintype "passive"))
      (node (ref "RP4") (pin "6") (pinfunction "6_6") (pintype "passive"))
    )
    (net (code "61") (name "/MD_D5") (class "Default")
      (node (ref "B1") (pin "A25") (pinfunction "VD5_A25") (pintype "passive"))
      (node (ref "RP3") (pin "4") (pinfunction "4_4") (pintype "passive"))
    )
    (net (code "62") (name "/MD_D6") (class "Default")
      (node (ref "B1") (pin "A22") (pinfunction "VD6_A22") (pintype "passive"))
      (node (ref "RP2") (pin "8") (pinfunction "8_8") (pintype "passive"))
    )
    (net (code "63") (name "/MD_D7") (class "Default")
      (node (ref "B1") (pin "A19") (pinfunction "VD7_A19") (pintype "passive"))
      (node (ref "RP1") (pin "8") (pinfunction "8_8") (pintype "passive"))
    )
    (net (code "64") (name "/MD_D8") (class "Default")
      (node (ref "B1") (pin "A21") (pinfunction "VD8_A21") (pintype "passive"))
      (node (ref "RP1") (pin "4") (pinfunction "4_4") (pintype "passive"))
    )
    (net (code "65") (name "/MD_D9") (class "Default")
      (node (ref "B1") (pin "A24") (pinfunction "VD9_A24") (pintype "passive"))
      (node (ref "RP3") (pin "8") (pinfunction "8_8") (pintype "passive"))
    )
    (net (code "66") (name "/MD_D10") (class "Default")
      (node (ref "B1") (pin "A27") (pinfunction "VD10_A27") (pintype "passive"))
      (node (ref "RP4") (pin "8") (pinfunction "8_8") (pintype "passive"))
    )
    (net (code "67") (name "/MD_D11") (class "Default")
      (node (ref "B1") (pin "A30") (pinfunction "VD11_A30") (pintype "passive"))
      (node (ref "RP4") (pin "2") (pinfunction "2_2") (pintype "passive"))
    )
    (net (code "68") (name "/MD_D12") (class "Default")
      (node (ref "B1") (pin "B25") (pinfunction "VD12_B25") (pintype "passive"))
      (node (ref "RP3") (pin "6") (pinfunction "6_6") (pintype "passive"))
    )
    (net (code "69") (name "/MD_D13") (class "Default")
      (node (ref "B1") (pin "B24") (pinfunction "VD13_B24") (pintype "passive"))
      (node (ref "RP2") (pin "2") (pinfunction "2_2") (pintype "passive"))
    )
    (net (code "70") (name "/MD_D14") (class "Default")
      (node (ref "B1") (pin "B23") (pinfunction "VD14_B23") (pintype "passive"))
      (node (ref "RP2") (pin "6") (pinfunction "6_6") (pintype "passive"))
    )
    (net (code "71") (name "/MD_D15") (class "Default")
      (node (ref "B1") (pin "B22") (pinfunction "VD15_B22") (pintype "passive"))
      (node (ref "RP1") (pin "2") (pinfunction "2_2") (pintype "passive"))
    )
    (net (code "72") (name "/MD_DTAK") (class "Default")
      (node (ref "B1") (pin "B20") (pinfunction "/DTAck_B20") (pintype "passive"))
      (node (ref "Q2") (pin "3") (pinfunction "DRAIN_3") (pintype "passive"))
    )
    (net (code "73") (name "/MD_LWR") (class "Default")
      (node (ref "B1") (pin "B28") (pinfunction "/LWr_B28") (pintype "passive"))
      (node (ref "U5") (pin "22") (pinfunction "B14_22") (pintype "bidirectional"))
    )
    (net (code "74") (name "/MD_MRES") (class "Default")
      (node (ref "B1") (pin "B2") (pinfunction "/MRES_B2") (pintype "passive"))
      (node (ref "R15") (pin "1") (pinfunction "1_1") (pintype "passive"))
      (node (ref "R16") (pin "1") (pinfunction "1_1") (pintype "passive"))
    )
    (net (code "75") (name "/MD_UWR") (class "Default")
      (node (ref "B1") (pin "B29") (pinfunction "/UWr_B29") (pintype "passive"))
      (node (ref "U5") (pin "23") (pinfunction "B15_23") (pintype "bidirectional"))
    )
    (net (code "76") (name "/MRES_G") (class "Default")
      (node (ref "Q1") (pin "1") (pinfunction "GATE_1") (pintype "passive"))
      (node (ref "U6") (pin "144") (pinfunction "IO_L1P_HSWAPEN_0_144") (pintype "bidirectional"))
    )
    (net (code "77") (name "/MRES_R") (class "Default")
      (node (ref "Q1") (pin "3") (pinfunction "DRAIN_3") (pintype "passive"))
      (node (ref "R16") (pin "2") (pinfunction "2_2") (pintype "passive"))
      (node (ref "U10") (pin "1") (pinfunction "A_1") (pintype "input"))
    )
    (net (code "78") (name "/NC0") (class "Default")
      (node (ref "U4") (pin "52") (pinfunction "PD0/FD[8]_52") (pintype "bidirectional"))
    )
    (net (code "79") (name "/NC1") (class "Default")
      (node (ref "U4") (pin "53") (pinfunction "PD1/FD[9]_53") (pintype "bidirectional"))
    )
    (net (code "80") (name "/NC2") (class "Default")
      (node (ref "U4") (pin "54") (pinfunction "PD2/FD[10]_54") (pintype "bidirectional"))
    )
    (net (code "81") (name "/NC3") (class "Default")
      (node (ref "U4") (pin "55") (pinfunction "PD3/FD[11]_55") (pintype "bidirectional"))
    )
    (net (code "82") (name "/NC4") (class "Default")
      (node (ref "U4") (pin "56") (pinfunction "PD4/FD[12]_56") (pintype "bidirectional"))
    )
    (net (code "83") (name "/NC5") (class "Default")
      (node (ref "U4") (pin "1") (pinfunction "PD5/FD[13]_1") (pintype "bidirectional"))
    )
    (net (code "84") (name "/NC6") (class "Default")
      (node (ref "U4") (pin "2") (pinfunction "PD6/FD[14]_2") (pintype "bidirectional"))
    )
    (net (code "85") (name "/NC7") (class "Default")
      (node (ref "U4") (pin "3") (pinfunction "PD7/FD[15]_3") (pintype "bidirectional"))
    )
    (net (code "86") (name "/PA1") (class "Default")
      (node (ref "U5") (pin "35") (pinfunction "A9_35") (pintype "bidirectional"))
      (node (ref "U6") (pin "12") (pinfunction "IO_L49P_3_12") (pintype "bidirectional"))
    )
    (net (code "87") (name "/PA2") (class "Default")
      (node (ref "U5") (pin "38") (pinfunction "A6_38") (pintype "bidirectional"))
      (node (ref "U6") (pin "9") (pinfunction "IO_L50N_3_9") (pintype "bidirectional"))
    )
    (net (code "88") (name "/PA3") (class "Default")
      (node (ref "U5") (pin "41") (pinfunction "A4_41") (pintype "bidirectional"))
      (node (ref "U6") (pin "7") (pinfunction "IO_L51N_3_7") (pintype "bidirectional"))
    )
    (net (code "89") (name "/PA4") (class "Default")
      (node (ref "U5") (pin "46") (pinfunction "A1_46") (pintype "bidirectional"))
      (node (ref "U6") (pin "2") (pinfunction "IO_L83P_3_2") (pintype "bidirectional"))
    )
    (net (code "90") (name "/PA5") (class "Default")
      (node (ref "U2") (pin "32") (pinfunction "A11_32") (pintype "bidirectional"))
      (node (ref "U6") (pin "141") (pinfunction "IO_L2N_0_141") (pintype "bidirectional"))
    )
    (net (code "91") (name "/PA6") (class "Default")
      (node (ref "U2") (pin "37") (pinfunction "A7_37") (pintype "bidirectional"))
      (node (ref "U6") (pin "137") (pinfunction "IO_L4N_0_137") (pintype "bidirectional"))
    )
    (net (code "92") (name "/PA7") (class "Default")
      (node (ref "U2") (pin "43") (pinfunction "A3_43") (pintype "bidirectional"))
      (node (ref "U6") (pin "133") (pinfunction "IO_L34N_GCLK18_0_133") (pintype "bidirectional"))
    )
    (net (code "93") (name "/PA8") (class "Default")
      (node (ref "U2") (pin "47") (pinfunction "A0_47") (pintype "bidirectional"))
      (node (ref "U6") (pin "131") (pinfunction "IO_L35N_GCLK16_0_131") (pintype "bidirectional"))
    )
    (net (code "94") (name "/PA9") (class "Default")
      (node (ref "U2") (pin "44") (pinfunction "A2_44") (pintype "bidirectional"))
      (node (ref "U6") (pin "127") (pinfunction "IO_L36P_GCLK15_0_127") (pintype "bidirectional"))
    )
    (net (code "95") (name "/PA10") (class "Default")
      (node (ref "U2") (pin "41") (pinfunction "A4_41") (pintype "bidirectional"))
      (node (ref "U6") (pin "126") (pinfunction "IO_L36N_GCLK14_0_126") (pintype "bidirectional"))
    )
    (net (code "96") (name "/PA11") (class "Default")
      (node (ref "U2") (pin "46") (pinfunction "A1_46") (pintype "bidirectional"))
      (node (ref "U6") (pin "132") (pinfunction "IO_L35P_GCLK17_0_132") (pintype "bidirectional"))
    )
    (net (code "97") (name "/PA12") (class "Default")
      (node (ref "U2") (pin "40") (pinfunction "A5_40") (pintype "bidirectional"))
      (node (ref "U6") (pin "134") (pinfunction "IO_L34P_GCLK19_0_134") (pintype "bidirectional"))
    )
    (net (code "98") (name "/PA13") (class "Default")
      (node (ref "U2") (pin "35") (pinfunction "A9_35") (pintype "bidirectional"))
      (node (ref "U6") (pin "139") (pinfunction "IO_L3N_0_139") (pintype "bidirectional"))
    )
    (net (code "99") (name "/PA14") (class "Default")
      (node (ref "U2") (pin "29") (pinfunction "A13_29") (pintype "bidirectional"))
      (node (ref "U6") (pin "143") (pinfunction "IO_L1N_VREF_0_143") (pintype "bidirectional"))
    )
    (net (code "100") (name "/PA15") (class "Default")
      (node (ref "U5") (pin "43") (pinfunction "A3_43") (pintype "bidirectional"))
      (node (ref "U6") (pin "6") (pinfunction "IO_L52P_3_6") (pintype "bidirectional"))
    )
    (net (code "101") (name "/PA16") (class "Default")
      (node (ref "U5") (pin "40") (pinfunction "A5_40") (pintype "bidirectional"))
      (node (ref "U6") (pin "8") (pinfunction "IO_L51P_3_8") (pintype "bidirectional"))
    )
    (net (code "102") (name "/PA17") (class "Default")
      (node (ref "U5") (pin "37") (pinfunction "A7_37") (pintype "bidirectional"))
      (node (ref "U6") (pin "10") (pinfunction "IO_L50P_3_10") (pintype "bidirectional"))
    )
    (net (code "103") (name "/PA18") (class "Default")
      (node (ref "U2") (pin "38") (pinfunction "A6_38") (pintype "bidirectional"))
      (node (ref "U6") (pin "124") (pinfunction "IO_L37P_GCLK13_0_124") (pintype "bidirectional"))
    )
    (net (code "104") (name "/PA19") (class "Default")
      (node (ref "U2") (pin "36") (pinfunction "A8_36") (pintype "bidirectional"))
      (node (ref "U6") (pin "138") (pinfunction "IO_L4P_0_138") (pintype "bidirectional"))
    )
    (net (code "105") (name "/PA20") (class "Default")
      (node (ref "U2") (pin "33") (pinfunction "A10_33") (pintype "bidirectional"))
      (node (ref "U6") (pin "140") (pinfunction "IO_L3P_0_140") (pintype "bidirectional"))
    )
    (net (code "106") (name "/PA21") (class "Default")
      (node (ref "U2") (pin "30") (pinfunction "A12_30") (pintype "bidirectional"))
      (node (ref "U6") (pin "142") (pinfunction "IO_L2P_0_142") (pintype "bidirectional"))
    )
    (net (code "107") (name "/PA22") (class "Default")
      (node (ref "U5") (pin "47") (pinfunction "A0_47") (pintype "bidirectional"))
      (node (ref "U6") (pin "1") (pinfunction "IO_L83N_VREF_3_1") (pintype "bidirectional"))
    )
    (net (code "108") (name "/PA23") (class "Default")
      (node (ref "U5") (pin "44") (pinfunction "A2_44") (pintype "bidirectional"))
      (node (ref "U6") (pin "5") (pinfunction "IO_L52N_3_5") (pintype "bidirectional"))
    )
    (net (code "109") (name "/PAS") (class "Default")
      (node (ref "R17") (pin "2") (pinfunction "2_2") (pintype "passive"))
      (node (ref "R18") (pin "2") (pinfunction "2_2") (pintype "passive"))
      (node (ref "U6") (pin "14") (pinfunction "IO_L44N_GCLK20_3_14") (pintype "bidirectional"))
    )
    (net (code "110") (name "/PD0") (class "Default")
      (node (ref "U6") (pin "21") (pinfunction "IO_L42N_GCLK24_3_21") (pintype "bidirectional"))
      (node (ref "U7") (pin "46") (pinfunction "A1_46") (pintype "bidirectional"))
    )
    (net (code "111") (name "/PD1") (class "Default")
      (node (ref "U6") (pin "27") (pinfunction "IO_L37P_3_27") (pintype "bidirectional"))
      (node (ref "U7") (pin "38") (pinfunction "A6_38") (pintype "bidirectional"))
    )
    (net (code "112") (name "/PD2") (class "Default")
      (node (ref "U6") (pin "34") (pinfunction "IO_L1N_VREF_3_34") (pintype "bidirectional"))
      (node (ref "U7") (pin "32") (pinfunction "A11_32") (pintype "bidirectional"))
    )
    (net (code "113") (name "/PD3") (class "Default")
      (node (ref "U6") (pin "43") (pinfunction "IO_L62N_D6_2_43") (pintype "bidirectional"))
      (node (ref "U7") (pin "27") (pinfunction "A14_27") (pintype "bidirectional"))
    )
    (net (code "114") (name "/PD4") (class "Default")
      (node (ref "U6") (pin "35") (pinfunction "IO_L1P_3_35") (pintype "bidirectional"))
      (node (ref "U7") (pin "29") (pinfunction "A13_29") (pintype "bidirectional"))
    )
    (net (code "115") (name "/PD5") (class "Default")
      (node (ref "U6") (pin "33") (pinfunction "IO_L2P_3_33") (pintype "bidirectional"))
      (node (ref "U7") (pin "33") (pinfunction "A10_33") (pintype "bidirectional"))
    )
    (net (code "116") (name "/PD6") (class "Default")
      (node (ref "U6") (pin "24") (pinfunction "IO_L41P_GCLK27_3_24") (pintype "bidirectional"))
      (node (ref "U7") (pin "41") (pinfunction "A4_41") (pintype "bidirectional"))
    )
    (net (code "117") (name "/PD7") (class "Default")
      (node (ref "U6") (pin "17") (pinfunction "IO_L43P_GCLK23_3_17") (pintype "bidirectional"))
      (node (ref "U7") (pin "47") (pinfunction "A0_47") (pintype "bidirectional"))
    )
    (net (code "118") (name "/PD8") (class "Default")
      (node (ref "U6") (pin "22") (pinfunction "IO_L42P_GCLK25_TRDY2_3_22") (pintype "bidirectional"))
      (node (ref "U7") (pin "44") (pinfunction "A2_44") (pintype "bidirectional"))
    )
    (net (code "119") (name "/PD9") (class "Default")
      (node (ref "U6") (pin "30") (pinfunction "IO_L36P_3_30") (pintype "bidirectional"))
      (node (ref "U7") (pin "36") (pinfunction "A8_36") (pintype "bidirectional"))
    )
    (net (code "120") (name "/PD10") (class "Default")
      (node (ref "U6") (pin "44") (pinfunction "IO_L62P_D5_2_44") (pintype "bidirectional"))
      (node (ref "U7") (pin "30") (pinfunction "A12_30") (pintype "bidirectional"))
    )
    (net (code "121") (name "/PD11") (class "Default")
      (node (ref "U6") (pin "41") (pinfunction "IO_L64P_D8_2_41") (pintype "bidirectional"))
      (node (ref "U7") (pin "26") (pinfunction "A15_26") (pintype "bidirectional"))
    )
    (net (code "122") (name "/PD12") (class "Default")
      (node (ref "U6") (pin "32") (pinfunction "IO_L2N_3_32") (pintype "bidirectional"))
      (node (ref "U7") (pin "35") (pinfunction "A9_35") (pintype "bidirectional"))
    )
    (net (code "123") (name "/PD13") (class "Default")
      (node (ref "U6") (pin "29") (pinfunction "IO_L36N_3_29") (pintype "bidirectional"))
      (node (ref "U7") (pin "37") (pinfunction "A7_37") (pintype "bidirectional"))
    )
    (net (code "124") (name "/PD14") (class "Default")
      (node (ref "U6") (pin "26") (pinfunction "IO_L37N_3_26") (pintype "bidirectional"))
      (node (ref "U7") (pin "40") (pinfunction "A5_40") (pintype "bidirectional"))
    )
    (net (code "125") (name "/PD15") (class "Default")
      (node (ref "U6") (pin "23") (pinfunction "IO_L41N_GCLK26_3_23") (pintype "bidirectional"))
      (node (ref "U7") (pin "43") (pinfunction "A3_43") (pintype "bidirectional"))
    )
    (net (code "126") (name "/POE") (class "Default")
      (node (ref "U5") (pin "36") (pinfunction "A8_36") (pintype "bidirectional"))
      (node (ref "U6") (pin "11") (pinfunction "IO_L49N_3_11") (pintype "bidirectional"))
    )
    (net (code "127") (name "/PWL") (class "Default")
      (node (ref "U5") (pin "27") (pinfunction "A14_27") (pintype "bidirectional"))
      (node (ref "U6") (pin "15") (pinfunction "IO_L44P_GCLK21_3_15") (pintype "bidirectional"))
    )
    (net (code "128") (name "/PWU") (class "Default")
      (node (ref "U5") (pin "26") (pinfunction "A15_26") (pintype "bidirectional"))
      (node (ref "U6") (pin "16") (pinfunction "IO_L43N_GCLK22_IRDY2_3_16") (pintype "bidirectional"))
    )
    (net (code "129") (name "/RAM_A0") (class "Default")
      (node (ref "U6") (pin "62") (pinfunction "IO_L12P_D1_MISO2_2_62") (pintype "bidirectional"))
      (node (ref "U8") (pin "23") (pinfunction "A0_23") (pintype "input"))
    )
    (net (code "130") (name "/RAM_A1") (class "Default")
      (node (ref "U6") (pin "61") (pinfunction "IO_L12N_D2_MISO3_2_61") (pintype "bidirectional"))
      (node (ref "U8") (pin "24") (pinfunction "A1_24") (pintype "input"))
    )
    (net (code "131") (name "/RAM_A2") (class "Default")
      (node (ref "R11") (pin "1") (pinfunction "1_1") (pintype "passive"))
      (node (ref "U6") (pin "60") (pinfunction "IO_L13P_M1_2_60") (pintype "bidirectional"))
      (node (ref "U8") (pin "25") (pinfunction "A2_25") (pintype "input"))
    )
    (net (code "132") (name "/RAM_A3") (class "Default")
      (node (ref "U6") (pin "59") (pinfunction "IO_L13N_D10_2_59") (pintype "bidirectional"))
      (node (ref "U8") (pin "26") (pinfunction "A3_26") (pintype "input"))
    )
    (net (code "133") (name "/RAM_A4") (class "Default")
      (node (ref "U6") (pin "57") (pinfunction "IO_L14N_D12_2_57") (pintype "bidirectional"))
      (node (ref "U8") (pin "29") (pinfunction "A4_29") (pintype "input"))
    )
    (net (code "134") (name "/RAM_A5") (class "Default")
      (node (ref "U6") (pin "56") (pinfunction "IO_L30P_GCLK1_D13_2_56") (pintype "bidirectional"))
      (node (ref "U8") (pin "30") (pinfunction "A5_30") (pintype "input"))
    )
    (net (code "135") (name "/RAM_A6") (class "Default")
      (node (ref "U6") (pin "55") (pinfunction "IO_L30N_GCLK0_USERCCLK_2_55") (pintype "bidirectional"))
      (node (ref "U8") (pin "31") (pinfunction "A6_31") (pintype "input"))
    )
    (net (code "136") (name "/RAM_A7") (class "Default")
      (node (ref "U6") (pin "51") (pinfunction "IO_L31P_GCLK31_D14_2_51") (pintype "bidirectional"))
      (node (ref "U8") (pin "32") (pinfunction "A7_32") (pintype "input"))
    )
    (net (code "137") (name "/RAM_A8") (class "Default")
      (node (ref "U6") (pin "50") (pinfunction "IO_L31N_GCLK30_D15_2_50") (pintype "bidirectional"))
      (node (ref "U8") (pin "33") (pinfunction "A8_33") (pintype "input"))
    )
    (net (code "138") (name "/RAM_A9") (class "Default")
      (node (ref "U6") (pin "48") (pinfunction "IO_L48P_D7_2_48") (pintype "bidirectional"))
      (node (ref "U8") (pin "34") (pinfunction "A9_34") (pintype "input"))
    )
    (net (code "139") (name "/RAM_A10") (class "Default")
      (node (ref "U6") (pin "66") (pinfunction "IO_L2N_CMPMOSI_2_66") (pintype "bidirectional"))
      (node (ref "U8") (pin "22") (pinfunction "A10_22") (pintype "input"))
    )
    (net (code "140") (name "/RAM_A11") (class "Default")
      (node (ref "U6") (pin "47") (pinfunction "IO_L48N_RDWR_B_VREF_2_47") (pintype "bidirectional"))
      (node (ref "U8") (pin "35") (pinfunction "A11_35") (pintype "input"))
    )
    (net (code "141") (name "/RAM_BA0") (class "Default")
      (node (ref "R10") (pin "2") (pinfunction "2_2") (pintype "passive"))
      (node (ref "U6") (pin "69") (pinfunction "IO_L1N_M0_CMPMISO_2_69") (pintype "bidirectional"))
      (node (ref "U8") (pin "20") (pinfunction "BA0_20") (pintype "input"))
    )
    (net (code "142") (name "/RAM_BA1") (class "Default")
      (node (ref "U6") (pin "67") (pinfunction "IO_L2P_CMPCLK_2_67") (pintype "bidirectional"))
      (node (ref "U8") (pin "21") (pinfunction "BA1_21") (pintype "input"))
    )
    (net (code "143") (name "/RAM_CAS") (class "Default")
      (node (ref "U6") (pin "75") (pinfunction "IO_L74P_AWAKE_1_75") (pintype "bidirectional"))
      (node (ref "U8") (pin "17") (pinfunction "CAS#_17") (pintype "input"))
    )
    (net (code "144") (name "/RAM_CLK") (class "Default")
      (node (ref "U6") (pin "58") (pinfunction "IO_L14P_D11_2_58") (pintype "bidirectional"))
      (node (ref "U8") (pin "38") (pinfunction "CLK_38") (pintype "input"))
    )
    (net (code "145") (name "/RAM_DQ0") (class "Default")
      (node (ref "U6") (pin "88") (pinfunction "IO_L42P_GCLK7_1_88") (pintype "bidirectional"))
      (node (ref "U8") (pin "2") (pinfunction "DQ0_2") (pintype "bidirectional"))
    )
    (net (code "146") (name "/RAM_DQ1") (class "Default")
      (node (ref "U6") (pin "87") (pinfunction "IO_L42N_GCLK6_TRDY1_1_87") (pintype "bidirectional"))
      (node (ref "U8") (pin "4") (pinfunction "DQ1_4") (pintype "bidirectional"))
    )
    (net (code "147") (name "/RAM_DQ2") (class "Default")
      (node (ref "U6") (pin "85") (pinfunction "IO_L43P_GCLK5_1_85") (pintype "bidirectional"))
      (node (ref "U8") (pin "5") (pinfunction "DQ2_5") (pintype "bidirectional"))
    )
    (net (code "148") (name "/RAM_DQ3") (class "Default")
      (node (ref "U6") (pin "84") (pinfunction "IO_L43N_GCLK4_1_84") (pintype "bidirectional"))
      (node (ref "U8") (pin "7") (pinfunction "DQ3_7") (pintype "bidirectional"))
    )
    (net (code "149") (name "/RAM_DQ4") (class "Default")
      (node (ref "U6") (pin "83") (pinfunction "IO_L45P_1_83") (pintype "bidirectional"))
      (node (ref "U8") (pin "8") (pinfunction "DQ4_8") (pintype "bidirectional"))
    )
    (net (code "150") (name "/RAM_DQ5") (class "Default")
      (node (ref "U6") (pin "82") (pinfunction "IO_L45N_1_82") (pintype "bidirectional"))
      (node (ref "U8") (pin "10") (pinfunction "DQ5_10") (pintype "bidirectional"))
    )
    (net (code "151") (name "/RAM_DQ6") (class "Default")
      (node (ref "U6") (pin "81") (pinfunction "IO_L46P_1_81") (pintype "bidirectional"))
      (node (ref "U8") (pin "11") (pinfunction "DQ6_11") (pintype "bidirectional"))
    )
    (net (code "152") (name "/RAM_DQ7") (class "Default")
      (node (ref "U6") (pin "80") (pinfunction "IO_L46N_1_80") (pintype "bidirectional"))
      (node (ref "U8") (pin "13") (pinfunction "DQ7_13") (pintype "bidirectional"))
    )
    (net (code "153") (name "/RAM_DQ8") (class "Default")
      (node (ref "U6") (pin "100") (pinfunction "IO_L33P_1_100") (pintype "bidirectional"))
      (node (ref "U8") (pin "42") (pinfunction "DQ8_42") (pintype "bidirectional"))
    )
    (net (code "154") (name "/RAM_DQ9") (class "Default")
      (node (ref "U6") (pin "99") (pinfunction "IO_L33N_1_99") (pintype "bidirectional"))
      (node (ref "U8") (pin "44") (pinfunction "DQ9_44") (pintype "bidirectional"))
    )
    (net (code "155") (name "/RAM_DQ10") (class "Default")
      (node (ref "U6") (pin "98") (pinfunction "IO_L34P_1_98") (pintype "bidirectional"))
      (node (ref "U8") (pin "45") (pinfunction "DQ10_45") (pintype "bidirectional"))
    )
    (net (code "156") (name "/RAM_DQ11") (class "Default")
      (node (ref "U6") (pin "97") (pinfunction "IO_L34N_1_97") (pintype "bidirectional"))
      (node (ref "U8") (pin "47") (pinfunction "DQ11_47") (pintype "bidirectional"))
    )
    (net (code "157") (name "/RAM_DQ12") (class "Default")
      (node (ref "U6") (pin "95") (pinfunction "IO_L40P_GCLK11_1_95") (pintype "bidirectional"))
      (node (ref "U8") (pin "48") (pinfunction "DQ12_48") (pintype "bidirectional"))
    )
    (net (code "158") (name "/RAM_DQ13") (class "Default")
      (node (ref "U6") (pin "94") (pinfunction "IO_L40N_GCLK10_1_94") (pintype "bidirectional"))
      (node (ref "U8") (pin "50") (pinfunction "DQ13_50") (pintype "bidirectional"))
    )
    (net (code "159") (name "/RAM_DQ14") (class "Default")
      (node (ref "U6") (pin "93") (pinfunction "IO_L41P_GCLK9_IRDY1_1_93") (pintype "bidirectional"))
      (node (ref "U8") (pin "51") (pinfunction "DQ14_51") (pintype "bidirectional"))
    )
    (net (code "160") (name "/RAM_DQ15") (class "Default")
      (node (ref "U6") (pin "92") (pinfunction "IO_L41N_GCLK8_1_92") (pintype "bidirectional"))
      (node (ref "U8") (pin "53") (pinfunction "DQ15_53") (pintype "bidirectional"))
    )
    (net (code "161") (name "/RAM_LDM") (class "Default")
      (node (ref "U6") (pin "79") (pinfunction "IO_L47P_1_79") (pintype "bidirectional"))
      (node (ref "U8") (pin "15") (pinfunction "DQML_15") (pintype "input"))
    )
    (net (code "162") (name "/RAM_RAS") (class "Default")
      (node (ref "U6") (pin "74") (pinfunction "IO_L74N_DOUT_BUSY_1_74") (pintype "bidirectional"))
      (node (ref "U8") (pin "18") (pinfunction "RAS#_18") (pintype "input"))
    )
    (net (code "163") (name "/RAM_UDM") (class "Default")
      (node (ref "U6") (pin "46") (pinfunction "IO_L49P_D3_2_46") (pintype "bidirectional"))
      (node (ref "U8") (pin "39") (pinfunction "DQMH_39") (pintype "input"))
    )
    (net (code "164") (name "/RAM_WE") (class "Default")
      (node (ref "U6") (pin "78") (pinfunction "IO_L47N_1_78") (pintype "bidirectional"))
      (node (ref "U8") (pin "16") (pinfunction "WE#_16") (pintype "input"))
    )
    (net (code "165") (name "/S6_DONE") (class "Default")
      (node (ref "R19") (pin "2") (pinfunction "2_2") (pintype "passive"))
      (node (ref "U10") (pin "2") (pinfunction "B_2") (pintype "input"))
      (node (ref "U6") (pin "71") (pinfunction "DONE_2_71") (pintype "bidirectional"))
    )
    (net (code "166") (name "/S6_TCK") (class "Default")
      (node (ref "U11") (pin "15") (pinfunction "Y_15") (pintype "bidirectional"))
      (node (ref "U6") (pin "109") (pinfunction "TCK_109") (pintype "input"))
    )
    (net (code "167") (name "/S6_TDI") (class "Default")
      (node (ref "U11") (pin "4") (pinfunction "Z_4") (pintype "bidirectional"))
      (node (ref "U6") (pin "110") (pinfunction "TDI_110") (pintype "input"))
    )
    (net (code "168") (name "/S6_TMS") (class "Default")
      (node (ref "U11") (pin "14") (pinfunction "X_14") (pintype "bidirectional"))
      (node (ref "U6") (pin "107") (pinfunction "TMS_107") (pintype "input"))
    )
    (net (code "169") (name "/SPI_CK") (class "Default")
      (node (ref "J2") (pin "5") (pinfunction "CLK_5") (pintype "passive"))
      (node (ref "U6") (pin "70") (pinfunction "IO_L1P_CCLK_2_70") (pintype "bidirectional"))
      (node (ref "U9") (pin "6") (pinfunction "C_6") (pintype "input"))
    )
    (net (code "170") (name "/SPI_MISO") (class "Default")
      (node (ref "J2") (pin "7") (pinfunction "DAT0_7") (pintype "passive"))
      (node (ref "U6") (pin "65") (pinfunction "IO_L3P_D0_DIN_MISO_MISO1_2_65") (pintype "bidirectional"))
      (node (ref "U9") (pin "2") (pinfunction "DQ1_2") (pintype "tri_state"))
    )
    (net (code "171") (name "/SPI_MOSI") (class "Default")
      (node (ref "J2") (pin "2") (pinfunction "CMD_2") (pintype "passive"))
      (node (ref "U6") (pin "64") (pinfunction "IO_L3N_MOSI_CSI_B_MISO0_2_64") (pintype "bidirectional"))
      (node (ref "U9") (pin "5") (pinfunction "DQ0_5") (pintype "input"))
    )
    (net (code "172") (name "/SPI_NVSS") (class "Default")
      (node (ref "U6") (pin "38") (pinfunction "IO_L65N_CSO_B_2_38") (pintype "bidirectional"))
      (node (ref "U9") (pin "1") (pinfunction "S#_1") (pintype "input"))
    )
    (net (code "173") (name "/SPI_SDSS") (class "Default")
      (node (ref "J2") (pin "1") (pinfunction "DAT3_1") (pintype "passive"))
      (node (ref "U6") (pin "45") (pinfunction "IO_L49N_D4_2_45") (pintype "bidirectional"))
    )
    (net (code "174") (name "/USB_D_N") (class "Default")
      (node (ref "J1") (pin "A7") (pinfunction "DM_A7") (pintype "passive"))
      (node (ref "J1") (pin "B7") (pinfunction "DM_B7") (pintype "passive"))
      (node (ref "U4") (pin "16") (pinfunction "DMINUS_16") (pintype "bidirectional"))
    )
    (net (code "175") (name "/USB_D_P") (class "Default")
      (node (ref "J1") (pin "A6") (pinfunction "DP_A6") (pintype "passive"))
      (node (ref "J1") (pin "B6") (pinfunction "DP_B6") (pintype "passive"))
      (node (ref "U4") (pin "15") (pinfunction "DPLUS_15") (pintype "bidirectional"))
    )
    (net (code "176") (name "1.2V") (class "Default")
      (node (ref "C11") (pin "2") (pinfunction "2_2") (pintype "passive"))
      (node (ref "C33") (pin "1") (pinfunction "1_1") (pintype "passive"))
      (node (ref "C38") (pin "2") (pinfunction "2_2") (pintype "passive"))
      (node (ref "C42") (pin "1") (pinfunction "1_1") (pintype "passive"))
      (node (ref "C44") (pin "1") (pinfunction "1_1") (pintype "passive"))
      (node (ref "C47") (pin "1") (pinfunction "1_1") (pintype "passive"))
      (node (ref "C53") (pin "1") (pinfunction "1_1") (pintype "passive"))
      (node (ref "L2") (pin "2") (pinfunction "2_2") (pintype "passive"))
      (node (ref "R3") (pin "2") (pinfunction "2_2") (pintype "passive"))
      (node (ref "U6") (pin "128") (pinfunction "VCCINT_128") (pintype "power_in"))
      (node (ref "U6") (pin "19") (pinfunction "VCCINT_19") (pintype "power_in"))
      (node (ref "U6") (pin "28") (pinfunction "VCCINT_28") (pintype "power_in"))
      (node (ref "U6") (pin "52") (pinfunction "VCCINT_52") (pintype "power_in"))
      (node (ref "U6") (pin "89") (pinfunction "VCCINT_89") (pintype "power_in"))
    )
    (net (code "177") (name "3.3V") (class "Default")
      (node (ref "C1") (pin "2") (pinfunction "2_2") (pintype "passive"))
      (node (ref "C13") (pin "1") (pinfunction "1_1") (pintype "passive"))
      (node (ref "C14") (pin "1") (pinfunction "1_1") (pintype "passive"))
      (node (ref "C15") (pin "1") (pinfunction "1_1") (pintype "passive"))
      (node (ref "C16") (pin "1") (pinfunction "1_1") (pintype "passive"))
      (node (ref "C17") (pin "1") (pinfunction "1_1") (pintype "passive"))
      (node (ref "C18") (pin "1") (pinfunction "1_1") (pintype "passive"))
      (node (ref "C22") (pin "1") (pinfunction "1_1") (pintype "passive"))
      (node (ref "C24") (pin "1") (pinfunction "1_1") (pintype "passive"))
      (node (ref "C25") (pin "1") (pinfunction "1_1") (pintype "passive"))
      (node (ref "C26") (pin "1") (pinfunction "1_1") (pintype "passive"))
      (node (ref "C27") (pin "1") (pinfunction "1_1") (pintype "passive"))
      (node (ref "C28") (pin "1") (pinfunction "1_1") (pintype "passive"))
      (node (ref "C29") (pin "1") (pinfunction "1_1") (pintype "passive"))
      (node (ref "C30") (pin "1") (pinfunction "1_1") (pintype "passive"))
      (node (ref "C31") (pin "2") (pinfunction "2_2") (pintype "passive"))
      (node (ref "C32") (pin "2") (pinfunction "2_2") (pintype "passive"))
      (node (ref "C34") (pin "2") (pinfunction "2_2") (pintype "passive"))
      (node (ref "C35") (pin "1") (pinfunction "1_1") (pintype "passive"))
      (node (ref "C36") (pin "1") (pinfunction "1_1") (pintype "passive"))
      (node (ref "C37") (pin "1") (pinfunction "1_1") (pintype "passive"))
      (node (ref "C39") (pin "2") (pinfunction "2_2") (pintype "passive"))
      (node (ref "C40") (pin "1") (pinfunction "1_1") (pintype "passive"))
      (node (ref "C41") (pin "2") (pinfunction "2_2") (pintype "passive"))
      (node (ref "C43") (pin "2") (pinfunction "2_2") (pintype "passive"))
      (node (ref "C48") (pin "1") (pinfunction "1_1") (pintype "passive"))
      (node (ref "C49") (pin "1") (pinfunction "1_1") (pintype "passive"))
      (node (ref "C50") (pin "2") (pinfunction "2_2") (pintype "passive"))
      (node (ref "C51") (pin "2") (pinfunction "2_2") (pintype "passive"))
      (node (ref "C52") (pin "1") (pinfunction "1_1") (pintype "passive"))
      (node (ref "C54") (pin "1") (pinfunction "1_1") (pintype "passive"))
      (node (ref "C55") (pin "2") (pinfunction "2_2") (pintype "passive"))
      (node (ref "C56") (pin "2") (pinfunction "2_2") (pintype "passive"))
      (node (ref "C57") (pin "2") (pinfunction "2_2") (pintype "passive"))
      (node (ref "C58") (pin "2") (pinfunction "2_2") (pintype "passive"))
      (node (ref "C59") (pin "2") (pinfunction "2_2") (pintype "passive"))
      (node (ref "C60") (pin "2") (pinfunction "2_2") (pintype "passive"))
      (node (ref "C61") (pin "2") (pinfunction "2_2") (pintype "passive"))
      (node (ref "C62") (pin "2") (pinfunction "2_2") (pintype "passive"))
      (node (ref "C63") (pin "2") (pinfunction "2_2") (pintype "passive"))
      (node (ref "C9") (pin "1") (pinfunction "1_1") (pintype "passive"))
      (node (ref "J2") (pin "4") (pinfunction "VDD_4") (pintype "power_in"))
      (node (ref "J3") (pin "2") (pinfunction "VREF_2") (pintype "passive"))
      (node (ref "L1") (pin "1") (pinfunction "1_1") (pintype "passive"))
      (node (ref "R10") (pin "1") (pinfunction "1_1") (pintype "passive"))
      (node (ref "R12") (pin "2") (pinfunction "2_2") (pintype "passive"))
      (node (ref "R13") (pin "1") (pinfunction "1_1") (pintype "passive"))
      (node (ref "R19") (pin "1") (pinfunction "1_1") (pintype "passive"))
      (node (ref "R2") (pin "1") (pinfunction "1_1") (pintype "passive"))
      (node (ref "R20") (pin "1") (pinfunction "1_1") (pintype "passive"))
      (node (ref "R23") (pin "1") (pinfunction "1_1") (pintype "passive"))
      (node (ref "R5") (pin "1") (pinfunction "1_1") (pintype "passive"))
      (node (ref "R8") (pin "2") (pinfunction "2_2") (pintype "passive"))
      (node (ref "R9") (pin "2") (pinfunction "2_2") (pintype "passive"))
      (node (ref "U10") (pin "5") (pinfunction "VCC_5") (pintype "power_in"))
      (node (ref "U11") (pin "16") (pinfunction "VDD_16") (pintype "power_in"))
      (node (ref "U2") (pin "18") (pinfunction "VDD_18") (pintype "power_in"))
      (node (ref "U2") (pin "31") (pinfunction "VDD_31") (pintype "power_in"))
      (node (ref "U2") (pin "42") (pinfunction "VDD_42") (pintype "power_in"))
      (node (ref "U2") (pin "7") (pinfunction "VDD_7") (pintype "power_in"))
      (node (ref "U3") (pin "1") (pinfunction "A0_1") (pintype "input"))
      (node (ref "U3") (pin "8") (pinfunction "VCC_8") (pintype "power_in"))
      (node (ref "U4") (pin "10") (pinfunction "AVCC_10") (pintype "power_in"))
      (node (ref "U4") (pin "14") (pinfunction "AVCC_14") (pintype "power_in"))
      (node (ref "U4") (pin "18") (pinfunction "VCC_18") (pintype "power_in"))
      (node (ref "U4") (pin "24") (pinfunction "VCC_24") (pintype "power_in"))
      (node (ref "U4") (pin "34") (pinfunction "VCC_34") (pintype "power_in"))
      (node (ref "U4") (pin "39") (pinfunction "VCC_39") (pintype "power_in"))
      (node (ref "U4") (pin "50") (pinfunction "VCC_50") (pintype "power_in"))
      (node (ref "U4") (pin "6") (pinfunction "VCC_6") (pintype "power_in"))
      (node (ref "U5") (pin "18") (pinfunction "VDD_18") (pintype "power_in"))
      (node (ref "U5") (pin "19") (pinfunction "B12_19") (pintype "bidirectional"))
      (node (ref "U5") (pin "31") (pinfunction "VDD_31") (pintype "power_in"))
      (node (ref "U5") (pin "42") (pinfunction "VDD_42") (pintype "power_in"))
      (node (ref "U5") (pin "7") (pinfunction "VDD_7") (pintype "power_in"))
      (node (ref "U6") (pin "103") (pinfunction "VCCO_1_103") (pintype "power_in"))
      (node (ref "U6") (pin "122") (pinfunction "VCCO_0_122") (pintype "power_in"))
      (node (ref "U6") (pin "125") (pinfunction "VCCO_0_125") (pintype "power_in"))
      (node (ref "U6") (pin "129") (pinfunction "VCCAUX_129") (pintype "power_in"))
      (node (ref "U6") (pin "135") (pinfunction "VCCO_0_135") (pintype "power_in"))
      (node (ref "U6") (pin "18") (pinfunction "VCCO_3_18") (pintype "power_in"))
      (node (ref "U6") (pin "20") (pinfunction "VCCAUX_20") (pintype "power_in"))
      (node (ref "U6") (pin "31") (pinfunction "VCCO_3_31") (pintype "power_in"))
      (node (ref "U6") (pin "36") (pinfunction "VCCAUX_36") (pintype "power_in"))
      (node (ref "U6") (pin "4") (pinfunction "VCCO_3_4") (pintype "power_in"))
      (node (ref "U6") (pin "42") (pinfunction "VCCO_2_42") (pintype "power_in"))
      (node (ref "U6") (pin "53") (pinfunction "VCCAUX_53") (pintype "power_in"))
      (node (ref "U6") (pin "63") (pinfunction "VCCO_2_63") (pintype "power_in"))
      (node (ref "U6") (pin "76") (pinfunction "VCCO_1_76") (pintype "power_in"))
      (node (ref "U6") (pin "86") (pinfunction "VCCO_1_86") (pintype "power_in"))
      (node (ref "U6") (pin "90") (pinfunction "VCCAUX_90") (pintype "power_in"))
      (node (ref "U7") (pin "31") (pinfunction "VDD_31") (pintype "power_in"))
      (node (ref "U7") (pin "42") (pinfunction "VDD_42") (pintype "power_in"))
      (node (ref "U8") (pin "1") (pinfunction "VDD_1") (pintype "power_in"))
      (node (ref "U8") (pin "14") (pinfunction "VDD_14") (pintype "power_in"))
      (node (ref "U8") (pin "27") (pinfunction "VDD_27") (pintype "power_in"))
      (node (ref "U8") (pin "3") (pinfunction "VDDQ_3") (pintype "power_in"))
      (node (ref "U8") (pin "37") (pinfunction "CKE_37") (pintype "input"))
      (node (ref "U8") (pin "43") (pinfunction "VDDQ_43") (pintype "power_in"))
      (node (ref "U8") (pin "49") (pinfunction "VDDQ_49") (pintype "power_in"))
      (node (ref "U8") (pin "9") (pinfunction "VDDQ_9") (pintype "power_in"))
      (node (ref "U9") (pin "8") (pinfunction "VCC_8") (pintype "power_in"))
    )
    (net (code "178") (name "5V") (class "Default")
      (node (ref "C3") (pin "2") (pinfunction "2_2") (pintype "passive"))
      (node (ref "C4") (pin "2") (pinfunction "2_2") (pintype "passive"))
      (node (ref "C6") (pin "1") (pinfunction "1_1") (pintype "passive"))
      (node (ref "C7") (pin "2") (pinfunction "2_2") (pintype "passive"))
      (node (ref "C8") (pin "1") (pinfunction "1_1") (pintype "passive"))
      (node (ref "L3") (pin "2") (pinfunction "2_2") (pintype "passive"))
      (node (ref "U1") (pin "1") (pinfunction "EN1_1") (pintype "input"))
      (node (ref "U1") (pin "3") (pinfunction "VIN2_3") (pintype "power_in"))
      (node (ref "U1") (pin "6") (pinfunction "EN2_6") (pintype "input"))
      (node (ref "U1") (pin "8") (pinfunction "VIN1_8") (pintype "power_in"))
    )
    (net (code "179") (name "5VMD") (class "Default")
      (node (ref "B1") (pin "A2") (pinfunction "Vcc1_A2") (pintype "passive"))
      (node (ref "B1") (pin "A31") (pinfunction "Vcc1_A31") (pintype "passive"))
      (node (ref "C2") (pin "2") (pinfunction "2_2") (pintype "passive"))
      (node (ref "D2") (pin "2") (pinfunction "A_2") (pintype "passive"))
      (node (ref "R14") (pin "1") (pinfunction "1_1") (pintype "passive"))
      (node (ref "R15") (pin "2") (pinfunction "2_2") (pintype "passive"))
    )
    (net (code "180") (name "5VUSB") (class "Default")
      (node (ref "D1") (pin "2") (pinfunction "A_2") (pintype "passive"))
      (node (ref "J1") (pin "A4") (pinfunction "VBUS_A4") (pintype "passive"))
      (node (ref "J1") (pin "A9") (pinfunction "VBUS_A9") (pintype "passive"))
      (node (ref "J1") (pin "B4") (pinfunction "VBUS_B4") (pintype "passive"))
      (node (ref "J1") (pin "B9") (pinfunction "VBUS_B9") (pintype "passive"))
      (node (ref "R6") (pin "1") (pinfunction "1_1") (pintype "passive"))
    )
    (net (code "181") (name "GND") (class "Default")
      (node (ref "B1") (pin "A1") (pinfunction "Gnd_A1") (pintype "passive"))
      (node (ref "B1") (pin "A18") (pinfunction "Gnd_A18") (pintype "passive"))
      (node (ref "B1") (pin "A32") (pinfunction "Gnd_A32") (pintype "passive"))
      (node (ref "B1") (pin "B32") (pinfunction "/Cart_B32") (pintype "passive"))
      (node (ref "C1") (pin "1") (pinfunction "1_1") (pintype "passive"))
      (node (ref "C11") (pin "1") (pinfunction "1_1") (pintype "passive"))
      (node (ref "C13") (pin "2") (pinfunction "2_2") (pintype "passive"))
      (node (ref "C14") (pin "2") (pinfunction "2_2") (pintype "passive"))
      (node (ref "C15") (pin "2") (pinfunction "2_2") (pintype "passive"))
      (node (ref "C16") (pin "2") (pinfunction "2_2") (pintype "passive"))
      (node (ref "C17") (pin "2") (pinfunction "2_2") (pintype "passive"))
      (node (ref "C18") (pin "2") (pinfunction "2_2") (pintype "passive"))
      (node (ref "C19") (pin "2") (pinfunction "2_2") (pintype "passive"))
      (node (ref "C2") (pin "1") (pinfunction "1_1") (pintype "passive"))
      (node (ref "C20") (pin "2") (pinfunction "2_2") (pintype "passive"))
      (node (ref "C21") (pin "2") (pinfunction "2_2") (pintype "passive"))
      (node (ref "C22") (pin "2") (pinfunction "2_2") (pintype "passive"))
      (node (ref "C23") (pin "2") (pinfunction "2_2") (pintype "passive"))
      (node (ref "C24") (pin "2") (pinfunction "2_2") (pintype "passive"))
      (node (ref "C25") (pin "2") (pinfunction "2_2") (pintype "passive"))
      (node (ref "C26") (pin "2") (pinfunction "2_2") (pintype "passive"))
      (node (ref "C27") (pin "2") (pinfunction "2_2") (pintype "passive"))
      (node (ref "C28") (pin "2") (pinfunction "2_2") (pintype "passive"))
      (node (ref "C29") (pin "2") (pinfunction "2_2") (pintype "passive"))
      (node (ref "C3") (pin "1") (pinfunction "1_1") (pintype "passive"))
      (node (ref "C30") (pin "2") (pinfunction "2_2") (pintype "passive"))
      (node (ref "C31") (pin "1") (pinfunction "1_1") (pintype "passive"))
      (node (ref "C32") (pin "1") (pinfunction "1_1") (pintype "passive"))
      (node (ref "C33") (pin "2") (pinfunction "2_2") (pintype "passive"))
      (node (ref "C34") (pin "1") (pinfunction "1_1") (pintype "passive"))
      (node (ref "C35") (pin "2") (pinfunction "2_2") (pintype "passive"))
      (node (ref "C36") (pin "2") (pinfunction "2_2") (pintype "passive"))
      (node (ref "C37") (pin "2") (pinfunction "2_2") (pintype "passive"))
      (node (ref "C38") (pin "1") (pinfunction "1_1") (pintype "passive"))
      (node (ref "C39") (pin "1") (pinfunction "1_1") (pintype "passive"))
      (node (ref "C4") (pin "1") (pinfunction "1_1") (pintype "passive"))
      (node (ref "C40") (pin "2") (pinfunction "2_2") (pintype "passive"))
      (node (ref "C41") (pin "1") (pinfunction "1_1") (pintype "passive"))
      (node (ref "C42") (pin "2") (pinfunction "2_2") (pintype "passive"))
      (node (ref "C43") (pin "1") (pinfunction "1_1") (pintype "passive"))
      (node (ref "C44") (pin "2") (pinfunction "2_2") (pintype "passive"))
      (node (ref "C45") (pin "2") (pinfunction "2_2") (pintype "passive"))
      (node (ref "C46") (pin "1") (pinfunction "1_1") (pintype "passive"))
      (node (ref "C47") (pin "2") (pinfunction "2_2") (pintype "passive"))
      (node (ref "C48") (pin "2") (pinfunction "2_2") (pintype "passive"))
      (node (ref "C49") (pin "2") (pinfunction "2_2") (pintype "passive"))
      (node (ref "C5") (pin "1") (pinfunction "1_1") (pintype "passive"))
      (node (ref "C50") (pin "1") (pinfunction "1_1") (pintype "passive"))
      (node (ref "C51") (pin "1") (pinfunction "1_1") (pintype "passive"))
      (node (ref "C52") (pin "2") (pinfunction "2_2") (pintype "passive"))
      (node (ref "C53") (pin "2") (pinfunction "2_2") (pintype "passive"))
      (node (ref "C54") (pin "2") (pinfunction "2_2") (pintype "passive"))
      (node (ref "C55") (pin "1") (pinfunction "1_1") (pintype "passive"))
      (node (ref "C56") (pin "1") (pinfunction "1_1") (pintype "passive"))
      (node (ref "C57") (pin "1") (pinfunction "1_1") (pintype "passive"))
      (node (ref "C58") (pin "1") (pinfunction "1_1") (pintype "passive"))
      (node (ref "C59") (pin "1") (pinfunction "1_1") (pintype "passive"))
      (node (ref "C6") (pin "2") (pinfunction "2_2") (pintype "passive"))
      (node (ref "C60") (pin "1") (pinfunction "1_1") (pintype "passive"))
      (node (ref "C61") (pin "1") (pinfunction "1_1") (pintype "passive"))
      (node (ref "C62") (pin "1") (pinfunction "1_1") (pintype "passive"))
      (node (ref "C63") (pin "1") (pinfunction "1_1") (pintype "passive"))
      (node (ref "C7") (pin "1") (pinfunction "1_1") (pintype "passive"))
      (node (ref "C8") (pin "2") (pinfunction "2_2") (pintype "passive"))
      (node (ref "C9") (pin "2") (pinfunction "2_2") (pintype "passive"))
      (node (ref "J1") (pin "A1") (pinfunction "GND_A1") (pintype "passive"))
      (node (ref "J1") (pin "A12") (pinfunction "GND_A12") (pintype "passive"))
      (node (ref "J1") (pin "B1") (pinfunction "GND_B1") (pintype "passive"))
      (node (ref "J1") (pin "B12") (pinfunction "GND_B12") (pintype "passive"))
      (node (ref "J1") (pin "G1") (pinfunction "GND_G1") (pintype "passive"))
      (node (ref "J1") (pin "G2") (pinfunction "GND_G2") (pintype "passive"))
      (node (ref "J1") (pin "T1") (pinfunction "TAB_T1") (pintype "passive"))
      (node (ref "J1") (pin "T2") (pinfunction "TAB_T2") (pintype "passive"))
      (node (ref "J1") (pin "T3") (pinfunction "TAB_T3") (pintype "passive"))
      (node (ref "J1") (pin "T4") (pinfunction "TAB_T4") (pintype "passive"))
      (node (ref "J2") (pin "10") (pinfunction "CARD_10") (pintype "passive"))
      (node (ref "J2") (pin "11") (pinfunction "GND_11") (pintype "power_in"))
      (node (ref "J2") (pin "12") (pinfunction "GND_12") (pintype "power_in"))
      (node (ref "J2") (pin "13") (pinfunction "GND_13") (pintype "power_in"))
      (node (ref "J2") (pin "14") (pinfunction "GND_14") (pintype "power_in"))
      (node (ref "J2") (pin "3") (pinfunction "GND_3") (pintype "power_in"))
      (node (ref "J2") (pin "6") (pinfunction "GND_6") (pintype "power_in"))
      (node (ref "J3") (pin "11") (pinfunction "GND_11") (pintype "passive"))
      (node (ref "J3") (pin "3") (pinfunction "GND_3") (pintype "passive"))
      (node (ref "J3") (pin "5") (pinfunction "GND_5") (pintype "passive"))
      (node (ref "J3") (pin "7") (pinfunction "GND_7") (pintype "passive"))
      (node (ref "J3") (pin "9") (pinfunction "GND_9") (pintype "passive"))
      (node (ref "Q1") (pin "2") (pinfunction "SOURCE_2") (pintype "passive"))
      (node (ref "Q2") (pin "2") (pinfunction "SOURCE_2") (pintype "passive"))
      (node (ref "R1") (pin "2") (pinfunction "2_2") (pintype "passive"))
      (node (ref "R11") (pin "2") (pinfunction "2_2") (pintype "passive"))
      (node (ref "R21") (pin "2") (pinfunction "2_2") (pintype "passive"))
      (node (ref "R22") (pin "1") (pinfunction "1_1") (pintype "passive"))
      (node (ref "R4") (pin "2") (pinfunction "2_2") (pintype "passive"))
      (node (ref "R7") (pin "2") (pinfunction "2_2") (pintype "passive"))
      (node (ref "U1") (pin "11") (pinfunction "PGND_11") (pintype "power_in"))
      (node (ref "U1") (pin "4") (pinfunction "GND_4") (pintype "power_in"))
      (node (ref "U1") (pin "9") (pinfunction "GND_9") (pintype "power_in"))
      (node (ref "U10") (pin "3") (pinfunction "GND_3") (pintype "power_in"))
      (node (ref "U11") (pin "6") (pinfunction "~{EN}_6") (pintype "input"))
      (node (ref "U11") (pin "7") (pinfunction "VEE_7") (pintype "power_in"))
      (node (ref "U11") (pin "8") (pinfunction "GND_8") (pintype "power_in"))
      (node (ref "U2") (pin "1") (pinfunction "T/R~{1}_1") (pintype "input"))
      (node (ref "U2") (pin "10") (pinfunction "GND_10") (pintype "power_in"))
      (node (ref "U2") (pin "15") (pinfunction "GND_15") (pintype "power_in"))
      (node (ref "U2") (pin "21") (pinfunction "GND_21") (pintype "power_in"))
      (node (ref "U2") (pin "22") (pinfunction "B14_22") (pintype "bidirectional"))
      (node (ref "U2") (pin "23") (pinfunction "B15_23") (pintype "bidirectional"))
      (node (ref "U2") (pin "24") (pinfunction "T/~{R}2_24") (pintype "input"))
      (node (ref "U2") (pin "25") (pinfunction "~{OE}2_25") (pintype "input"))
      (node (ref "U2") (pin "28") (pinfunction "GND_28") (pintype "power_in"))
      (node (ref "U2") (pin "34") (pinfunction "GND_34") (pintype "power_in"))
      (node (ref "U2") (pin "39") (pinfunction "GND_39") (pintype "power_in"))
      (node (ref "U2") (pin "4") (pinfunction "GND_4") (pintype "power_in"))
      (node (ref "U2") (pin "45") (pinfunction "GND_45") (pintype "power_in"))
      (node (ref "U2") (pin "48") (pinfunction "~{OE}1_48") (pintype "input"))
      (node (ref "U3") (pin "2") (pinfunction "A1_2") (pintype "input"))
      (node (ref "U3") (pin "3") (pinfunction "A2_3") (pintype "input"))
      (node (ref "U3") (pin "4") (pinfunction "VSS_4") (pintype "power_in"))
      (node (ref "U3") (pin "7") (pinfunction "WP_7") (pintype "input"))
      (node (ref "U4") (pin "13") (pinfunction "AGND_13") (pintype "power_in"))
      (node (ref "U4") (pin "17") (pinfunction "AGND_17") (pintype "power_in"))
      (node (ref "U4") (pin "19") (pinfunction "GND_19") (pintype "power_in"))
      (node (ref "U4") (pin "21") (pinfunction "RESERVED_21") (pintype "input"))
      (node (ref "U4") (pin "33") (pinfunction "GND_33") (pintype "power_in"))
      (node (ref "U4") (pin "35") (pinfunction "GND_35") (pintype "power_in"))
      (node (ref "U4") (pin "4") (pinfunction "GND_4") (pintype "power_in"))
      (node (ref "U4") (pin "44") (pinfunction "PA4/FIFOADR0_44") (pintype "bidirectional"))
      (node (ref "U4") (pin "48") (pinfunction "GND_48") (pintype "power_in"))
      (node (ref "U4") (pin "7") (pinfunction "GND_7") (pintype "power_in"))
      (node (ref "U5") (pin "1") (pinfunction "T/R~{1}_1") (pintype "input"))
      (node (ref "U5") (pin "10") (pinfunction "GND_10") (pintype "power_in"))
      (node (ref "U5") (pin "15") (pinfunction "GND_15") (pintype "power_in"))
      (node (ref "U5") (pin "20") (pinfunction "B13_20") (pintype "bidirectional"))
      (node (ref "U5") (pin "21") (pinfunction "GND_21") (pintype "power_in"))
      (node (ref "U5") (pin "24") (pinfunction "T/~{R}2_24") (pintype "input"))
      (node (ref "U5") (pin "25") (pinfunction "~{OE}2_25") (pintype "input"))
      (node (ref "U5") (pin "28") (pinfunction "GND_28") (pintype "power_in"))
      (node (ref "U5") (pin "34") (pinfunction "GND_34") (pintype "power_in"))
      (node (ref "U5") (pin "39") (pinfunction "GND_39") (pintype "power_in"))
      (node (ref "U5") (pin "4") (pinfunction "GND_4") (pintype "power_in"))
      (node (ref "U5") (pin "45") (pinfunction "GND_45") (pintype "power_in"))
      (node (ref "U5") (pin "48") (pinfunction "~{OE}1_48") (pintype "input"))
      (node (ref "U6") (pin "108") (pinfunction "GND_108") (pintype "power_in"))
      (node (ref "U6") (pin "113") (pinfunction "GND_113") (pintype "power_in"))
      (node (ref "U6") (pin "13") (pinfunction "GND_13") (pintype "power_in"))
      (node (ref "U6") (pin "130") (pinfunction "GND_130") (pintype "power_in"))
      (node (ref "U6") (pin "136") (pinfunction "GND_136") (pintype "power_in"))
      (node (ref "U6") (pin "25") (pinfunction "GND_25") (pintype "power_in"))
      (node (ref "U6") (pin "3") (pinfunction "GND_3") (pintype "power_in"))
      (node (ref "U6") (pin "49") (pinfunction "GND_49") (pintype "power_in"))
      (node (ref "U6") (pin "54") (pinfunction "GND_54") (pintype "power_in"))
      (node (ref "U6") (pin "68") (pinfunction "GND_68") (pintype "power_in"))
      (node (ref "U6") (pin "73") (pinfunction "SUSPEND_73") (pintype "input"))
      (node (ref "U6") (pin "77") (pinfunction "GND_77") (pintype "power_in"))
      (node (ref "U6") (pin "91") (pinfunction "GND_91") (pintype "power_in"))
      (node (ref "U6") (pin "96") (pinfunction "GND_96") (pintype "power_in"))
      (node (ref "U7") (pin "10") (pinfunction "GND_10") (pintype "power_in"))
      (node (ref "U7") (pin "15") (pinfunction "GND_15") (pintype "power_in"))
      (node (ref "U7") (pin "21") (pinfunction "GND_21") (pintype "power_in"))
      (node (ref "U7") (pin "28") (pinfunction "GND_28") (pintype "power_in"))
      (node (ref "U7") (pin "34") (pinfunction "GND_34") (pintype "power_in"))
      (node (ref "U7") (pin "39") (pinfunction "GND_39") (pintype "power_in"))
      (node (ref "U7") (pin "4") (pinfunction "GND_4") (pintype "power_in"))
      (node (ref "U7") (pin "45") (pinfunction "GND_45") (pintype "power_in"))
      (node (ref "U8") (pin "12") (pinfunction "VSSQ_12") (pintype "power_in"))
      (node (ref "U8") (pin "19") (pinfunction "CS#_19") (pintype "input"))
      (node (ref "U8") (pin "28") (pinfunction "VSS_28") (pintype "power_in"))
      (node (ref "U8") (pin "41") (pinfunction "VSS_41") (pintype "power_in"))
      (node (ref "U8") (pin "46") (pinfunction "VSSQ_46") (pintype "power_in"))
      (node (ref "U8") (pin "52") (pinfunction "VSSQ_52") (pintype "power_in"))
      (node (ref "U8") (pin "54") (pinfunction "VSS_54") (pintype "power_in"))
      (node (ref "U8") (pin "6") (pinfunction "VSSQ_6") (pintype "power_in"))
      (node (ref "U9") (pin "4") (pinfunction "VSS_4") (pintype "power_in"))
    )
    (net (code "182") (name "Net-(C45-Pad1)") (class "Default")
      (node (ref "C45") (pin "1") (pinfunction "1_1") (pintype "passive"))
      (node (ref "C46") (pin "2") (pinfunction "2_2") (pintype "passive"))
      (node (ref "R13") (pin "2") (pinfunction "2_2") (pintype "passive"))
      (node (ref "R14") (pin "2") (pinfunction "2_2") (pintype "passive"))
      (node (ref "U7") (pin "18") (pinfunction "VDD_18") (pintype "power_in"))
      (node (ref "U7") (pin "7") (pinfunction "VDD_7") (pintype "power_in"))
    )
    (net (code "183") (name "Net-(D1-K)") (class "Default")
      (node (ref "C5") (pin "2") (pinfunction "2_2") (pintype "passive"))
      (node (ref "D1") (pin "1") (pinfunction "K_1") (pintype "passive"))
      (node (ref "D2") (pin "1") (pinfunction "K_1") (pintype "passive"))
      (node (ref "L3") (pin "1") (pinfunction "1_1") (pintype "passive"))
    )
    (net (code "184") (name "Net-(J1-CC1)") (class "Default")
      (node (ref "J1") (pin "A5") (pinfunction "CC1_A5") (pintype "passive"))
      (node (ref "R21") (pin "1") (pinfunction "1_1") (pintype "passive"))
    )
    (net (code "185") (name "Net-(J1-CC2)") (class "Default")
      (node (ref "J1") (pin "B5") (pinfunction "CC2_B5") (pintype "passive"))
      (node (ref "R22") (pin "2") (pinfunction "2_2") (pintype "passive"))
    )
    (net (code "186") (name "Net-(U1-FB1)") (class "Default")
      (node (ref "R3") (pin "1") (pinfunction "1_1") (pintype "passive"))
      (node (ref "R4") (pin "1") (pinfunction "1_1") (pintype "passive"))
      (node (ref "U1") (pin "2") (pinfunction "FB1_2") (pintype "passive"))
    )
    (net (code "187") (name "Net-(U1-FB2)") (class "Default")
      (node (ref "R1") (pin "1") (pinfunction "1_1") (pintype "passive"))
      (node (ref "R2") (pin "2") (pinfunction "2_2") (pintype "passive"))
      (node (ref "U1") (pin "7") (pinfunction "FB2_7") (pintype "passive"))
    )
    (net (code "188") (name "Net-(U1-LX1)") (class "Default")
      (node (ref "L2") (pin "1") (pinfunction "1_1") (pintype "passive"))
      (node (ref "U1") (pin "10") (pinfunction "LX1_10") (pintype "power_in"))
    )
    (net (code "189") (name "Net-(U1-LX2)") (class "Default")
      (node (ref "L1") (pin "2") (pinfunction "2_2") (pintype "passive"))
      (node (ref "U1") (pin "5") (pinfunction "LX2_5") (pintype "power_in"))
    )
    (net (code "190") (name "Net-(U4-XTALIN)") (class "Default")
      (node (ref "C23") (pin "1") (pinfunction "1_1") (pintype "passive"))
      (node (ref "U4") (pin "12") (pinfunction "XTALIN_12") (pintype "input"))
      (node (ref "Y1") (pin "2") (pinfunction "OUT_2") (pintype "passive"))
    )
    (net (code "191") (name "Net-(U4-XTALOUT)") (class "Default")
      (node (ref "C21") (pin "1") (pinfunction "1_1") (pintype "passive"))
      (node (ref "U4") (pin "11") (pinfunction "XTALOUT_11") (pintype "output"))
      (node (ref "Y1") (pin "1") (pinfunction "IN_1") (pintype "passive"))
    )
    (net (code "192") (name "Net-(U5-A10)") (class "Default")
      (node (ref "R17") (pin "1") (pinfunction "1_1") (pintype "passive"))
      (node (ref "U5") (pin "33") (pinfunction "A10_33") (pintype "bidirectional"))
    )
    (net (code "193") (name "Net-(U5-A11)") (class "Default")
      (node (ref "R18") (pin "1") (pinfunction "1_1") (pintype "passive"))
      (node (ref "U5") (pin "32") (pinfunction "A11_32") (pintype "bidirectional"))
    )
    (net (code "194") (name "Net-(U6E-PROGRAM_B_2)") (class "Default")
      (node (ref "R20") (pin "2") (pinfunction "2_2") (pintype "passive"))
      (node (ref "U6") (pin "37") (pinfunction "PROGRAM_B_2_37") (pintype "input"))
    )
    (net (code "195") (name "Net-(U7-B0)") (class "Default")
      (node (ref "RP1") (pin "7") (pinfunction "7_7") (pintype "passive"))
      (node (ref "U7") (pin "2") (pinfunction "B0_2") (pintype "bidirectional"))
    )
    (net (code "196") (name "Net-(U7-B1)") (class "Default")
      (node (ref "RP1") (pin "5") (pinfunction "5_5") (pintype "passive"))
      (node (ref "U7") (pin "3") (pinfunction "B1_3") (pintype "bidirectional"))
    )
    (net (code "197") (name "Net-(U7-B2)") (class "Default")
      (node (ref "RP1") (pin "3") (pinfunction "3_3") (pintype "passive"))
      (node (ref "U7") (pin "5") (pinfunction "B2_5") (pintype "bidirectional"))
    )
    (net (code "198") (name "Net-(U7-B3)") (class "Default")
      (node (ref "RP1") (pin "1") (pinfunction "1_1") (pintype "passive"))
      (node (ref "U7") (pin "6") (pinfunction "B3_6") (pintype "bidirectional"))
    )
    (net (code "199") (name "Net-(U7-B4)") (class "Default")
      (node (ref "RP2") (pin "7") (pinfunction "7_7") (pintype "passive"))
      (node (ref "U7") (pin "8") (pinfunction "B4_8") (pintype "bidirectional"))
    )
    (net (code "200") (name "Net-(U7-B5)") (class "Default")
      (node (ref "RP2") (pin "5") (pinfunction "5_5") (pintype "passive"))
      (node (ref "U7") (pin "9") (pinfunction "B5_9") (pintype "bidirectional"))
    )
    (net (code "201") (name "Net-(U7-B6)") (class "Default")
      (node (ref "RP2") (pin "3") (pinfunction "3_3") (pintype "passive"))
      (node (ref "U7") (pin "11") (pinfunction "B6_11") (pintype "bidirectional"))
    )
    (net (code "202") (name "Net-(U7-B7)") (class "Default")
      (node (ref "RP2") (pin "1") (pinfunction "1_1") (pintype "passive"))
      (node (ref "U7") (pin "12") (pinfunction "B7_12") (pintype "bidirectional"))
    )
    (net (code "203") (name "Net-(U7-B8)") (class "Default")
      (node (ref "RP3") (pin "7") (pinfunction "7_7") (pintype "passive"))
      (node (ref "U7") (pin "13") (pinfunction "B8_13") (pintype "bidirectional"))
    )
    (net (code "204") (name "Net-(U7-B9)") (class "Default")
      (node (ref "RP3") (pin "5") (pinfunction "5_5") (pintype "passive"))
      (node (ref "U7") (pin "14") (pinfunction "B9_14") (pintype "bidirectional"))
    )
    (net (code "205") (name "Net-(U7-B10)") (class "Default")
      (node (ref "RP3") (pin "3") (pinfunction "3_3") (pintype "passive"))
      (node (ref "U7") (pin "16") (pinfunction "B10_16") (pintype "bidirectional"))
    )
    (net (code "206") (name "Net-(U7-B11)") (class "Default")
      (node (ref "RP3") (pin "1") (pinfunction "1_1") (pintype "passive"))
      (node (ref "U7") (pin "17") (pinfunction "B11_17") (pintype "bidirectional"))
    )
    (net (code "207") (name "Net-(U7-B12)") (class "Default")
      (node (ref "RP4") (pin "7") (pinfunction "7_7") (pintype "passive"))
      (node (ref "U7") (pin "19") (pinfunction "B12_19") (pintype "bidirectional"))
    )
    (net (code "208") (name "Net-(U7-B13)") (class "Default")
      (node (ref "RP4") (pin "5") (pinfunction "5_5") (pintype "passive"))
      (node (ref "U7") (pin "20") (pinfunction "B13_20") (pintype "bidirectional"))
    )
    (net (code "209") (name "Net-(U7-B14)") (class "Default")
      (node (ref "RP4") (pin "3") (pinfunction "3_3") (pintype "passive"))
      (node (ref "U7") (pin "22") (pinfunction "B14_22") (pintype "bidirectional"))
    )
    (net (code "210") (name "Net-(U7-B15)") (class "Default")
      (node (ref "RP4") (pin "1") (pinfunction "1_1") (pintype "passive"))
      (node (ref "U7") (pin "23") (pinfunction "B15_23") (pintype "bidirectional"))
    )
    (net (code "211") (name "Net-(U9-HOLD#)") (class "Default")
      (node (ref "R12") (pin "1") (pinfunction "1_1") (pintype "passive"))
      (node (ref "U9") (pin "3") (pinfunction "W#_3") (pintype "input"))
      (node (ref "U9") (pin "7") (pinfunction "HOLD#_7") (pintype "input"))
    )
    (net (code "212") (name "Net-(U10A-Y)") (class "Default")
      (node (ref "U10") (pin "4") (pinfunction "Y_4") (pintype "output"))
      (node (ref "U7") (pin "25") (pinfunction "~{OE}2_25") (pintype "input"))
      (node (ref "U7") (pin "48") (pinfunction "~{OE}1_48") (pintype "input"))
    )
    (net (code "213") (name "unconnected-(B1-EDClk-PadB15)") (class "Default")
      (node (ref "B1") (pin "B15") (pinfunction "EDClk_B15") (pintype "passive"))
    )
    (net (code "214") (name "unconnected-(B1-SL1-PadB1)") (class "Default")
      (node (ref "B1") (pin "B1") (pinfunction "SL1_B1") (pintype "passive"))
    )
    (net (code "215") (name "unconnected-(B1-SR1-PadB3)") (class "Default")
      (node (ref "B1") (pin "B3") (pinfunction "SR1_B3") (pintype "passive"))
    )
    (net (code "216") (name "unconnected-(B1-VClk-PadB19)") (class "Default")
      (node (ref "B1") (pin "B19") (pinfunction "VClk_B19") (pintype "passive"))
    )
    (net (code "217") (name "unconnected-(B1-{slash}ASel-PadB26)") (class "Default")
      (node (ref "B1") (pin "B26") (pinfunction "/ASel_B26") (pintype "passive"))
    )
    (net (code "218") (name "unconnected-(B1-{slash}CAS2-PadB21)") (class "Default")
      (node (ref "B1") (pin "B21") (pinfunction "/CAS2_B21") (pintype "passive"))
    )
    (net (code "219") (name "unconnected-(B1-{slash}HSync-PadB14)") (class "Default")
      (node (ref "B1") (pin "B14") (pinfunction "/HSync_B14") (pintype "passive"))
    )
    (net (code "220") (name "unconnected-(B1-{slash}M3-PadB30)") (class "Default")
      (node (ref "B1") (pin "B30") (pinfunction "/M3_B30") (pintype "passive"))
    )
    (net (code "221") (name "unconnected-(B1-{slash}Time-PadB31)") (class "Default")
      (node (ref "B1") (pin "B31") (pinfunction "/Time_B31") (pintype "passive"))
    )
    (net (code "222") (name "unconnected-(B1-{slash}VRes-PadB27)") (class "Default")
      (node (ref "B1") (pin "B27") (pinfunction "/VRes_B27") (pintype "passive"))
    )
    (net (code "223") (name "unconnected-(B1-{slash}VSync-PadB13)") (class "Default")
      (node (ref "B1") (pin "B13") (pinfunction "/VSync_B13") (pintype "passive"))
    )
    (net (code "224") (name "unconnected-(B1-{slash}YS-PadB12)") (class "Default")
      (node (ref "B1") (pin "B12") (pinfunction "/YS_B12") (pintype "passive"))
    )
    (net (code "225") (name "unconnected-(J1-SBU1-PadA8)") (class "Default")
      (node (ref "J1") (pin "A8") (pinfunction "SBU1_A8") (pintype "passive+no_connect"))
    )
    (net (code "226") (name "unconnected-(J1-SBU2-PadB8)") (class "Default")
      (node (ref "J1") (pin "B8") (pinfunction "SBU2_B8") (pintype "passive+no_connect"))
    )
    (net (code "227") (name "unconnected-(J1-SS_1_RX_N-PadB10)") (class "Default")
      (node (ref "J1") (pin "B10") (pinfunction "SS_1_RX_N_B10") (pintype "passive+no_connect"))
    )
    (net (code "228") (name "unconnected-(J1-SS_1_RX_P-PadB11)") (class "Default")
      (node (ref "J1") (pin "B11") (pinfunction "SS_1_RX_P_B11") (pintype "passive+no_connect"))
    )
    (net (code "229") (name "unconnected-(J1-SS_1_TX_N-PadA3)") (class "Default")
      (node (ref "J1") (pin "A3") (pinfunction "SS_1_TX_N_A3") (pintype "passive+no_connect"))
    )
    (net (code "230") (name "unconnected-(J1-SS_1_TX_P-PadA2)") (class "Default")
      (node (ref "J1") (pin "A2") (pinfunction "SS_1_TX_P_A2") (pintype "passive+no_connect"))
    )
    (net (code "231") (name "unconnected-(J1-SS_2_RX_N-PadA10)") (class "Default")
      (node (ref "J1") (pin "A10") (pinfunction "SS_2_RX_N_A10") (pintype "passive+no_connect"))
    )
    (net (code "232") (name "unconnected-(J1-SS_2_RX_P-PadA11)") (class "Default")
      (node (ref "J1") (pin "A11") (pinfunction "SS_2_RX_P_A11") (pintype "passive+no_connect"))
    )
    (net (code "233") (name "unconnected-(J1-SS_2_TX_N-PadB3)") (class "Default")
      (node (ref "J1") (pin "B3") (pinfunction "SS_2_TX_N_B3") (pintype "passive+no_connect"))
    )
    (net (code "234") (name "unconnected-(J1-SS_2_TX_P-PadB2)") (class "Default")
      (node (ref "J1") (pin "B2") (pinfunction "SS_2_TX_P_B2") (pintype "passive+no_connect"))
    )
    (net (code "235") (name "unconnected-(J2-DAT1-Pad8)") (class "Default")
      (node (ref "J2") (pin "8") (pinfunction "DAT1_8") (pintype "passive+no_connect"))
    )
    (net (code "236") (name "unconnected-(J2-DAT2-Pad9)") (class "Default")
      (node (ref "J2") (pin "9") (pinfunction "DAT2_9") (pintype "passive+no_connect"))
    )
    (net (code "237") (name "unconnected-(J3-NC-Pad1)") (class "Default")
      (node (ref "J3") (pin "1") (pinfunction "NC_1") (pintype "passive+no_connect"))
    )
    (net (code "238") (name "unconnected-(J3-NC-Pad12)") (class "Default")
      (node (ref "J3") (pin "12") (pinfunction "NC_12") (pintype "passive+no_connect"))
    )
    (net (code "239") (name "unconnected-(J3-SRST-Pad14)") (class "Default")
      (node (ref "J3") (pin "14") (pinfunction "SRST_14") (pintype "passive+no_connect"))
    )
    (net (code "240") (name "unconnected-(U2-A14-Pad27)") (class "Default")
      (node (ref "U2") (pin "27") (pinfunction "A14_27") (pintype "bidirectional"))
    )
    (net (code "241") (name "unconnected-(U2-A15-Pad26)") (class "Default")
      (node (ref "U2") (pin "26") (pinfunction "A15_26") (pintype "bidirectional"))
    )
    (net (code "242") (name "unconnected-(U4-CLKOUT-Pad5)") (class "Default")
      (node (ref "U4") (pin "5") (pinfunction "CLKOUT_5") (pintype "output"))
    )
    (net (code "243") (name "unconnected-(U4-CTL0{slash}FLAGA-Pad36)") (class "Default")
      (node (ref "U4") (pin "36") (pinfunction "CTL0/FLAGA_36") (pintype "output"))
    )
    (net (code "244") (name "unconnected-(U5-A12-Pad30)") (class "Default")
      (node (ref "U5") (pin "30") (pinfunction "A12_30") (pintype "bidirectional"))
    )
    (net (code "245") (name "unconnected-(U5-A13-Pad29)") (class "Default")
      (node (ref "U5") (pin "29") (pinfunction "A13_29") (pintype "bidirectional"))
    )
    (net (code "246") (name "unconnected-(U6E-CMPCS_B_2-Pad72)") (class "Default")
      (node (ref "U6") (pin "72") (pinfunction "CMPCS_B_2_72") (pintype "input+no_connect"))
    )
    (net (code "247") (name "unconnected-(U8A-NC-Pad36)") (class "Default")
      (node (ref "U8") (pin "36") (pinfunction "NC_36") (pintype "passive"))
    )
    (net (code "248") (name "unconnected-(U8A-NC-Pad40)") (class "Default")
      (node (ref "U8") (pin "40") (pinfunction "NC_40") (pintype "passive"))
    )
  )
)
